# Drobit_V2_0.net
KiCad netlist of a schematic drawn in EAGLE
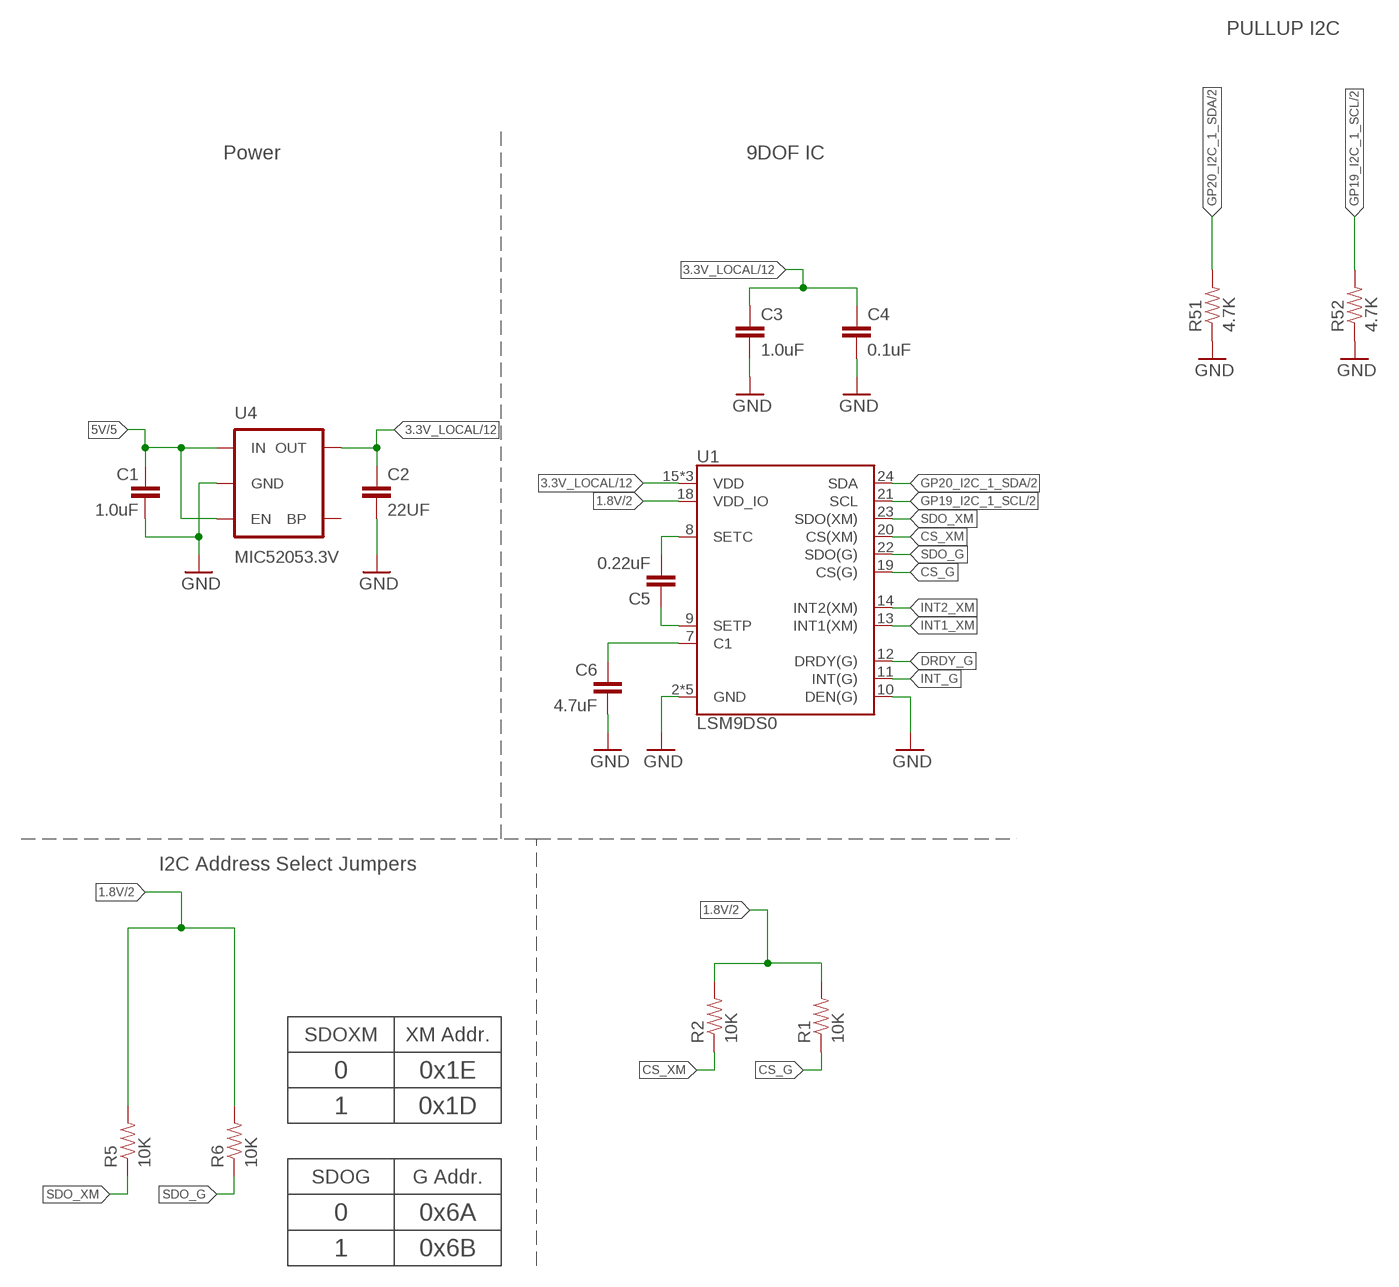
[diagram p0: schematic, sheet 1]
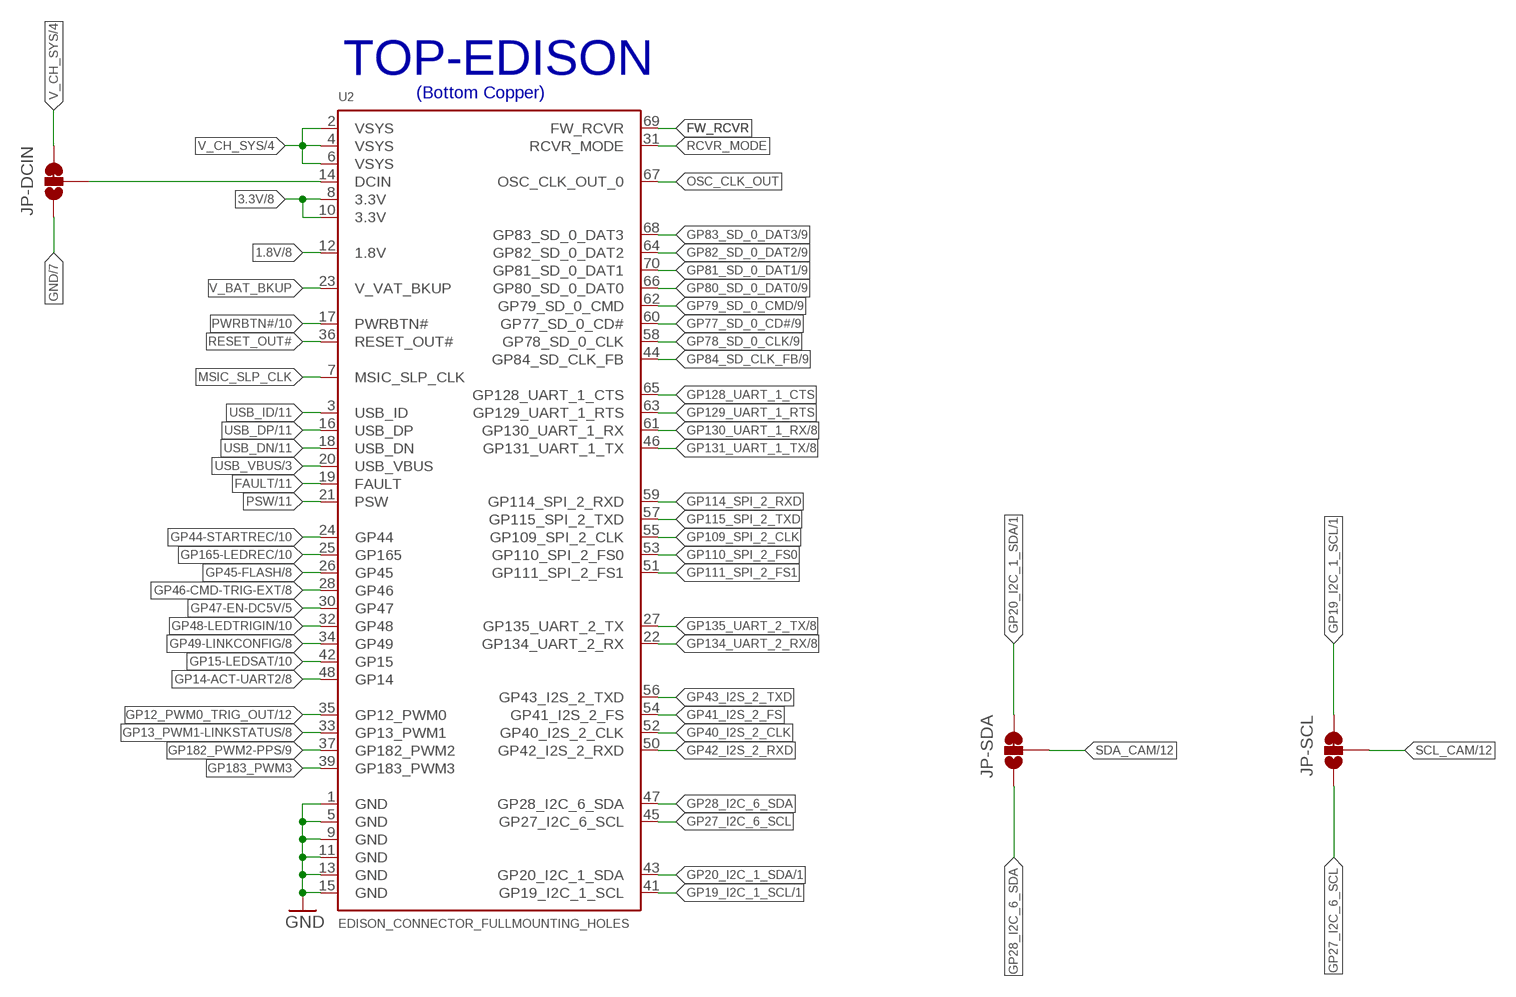
[diagram p1: schematic, sheet 2]
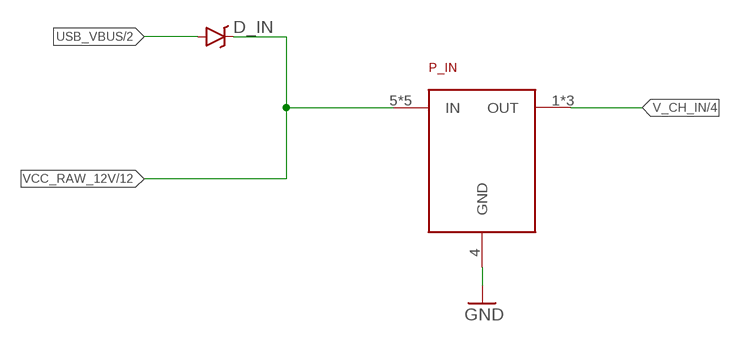
[diagram p2: schematic, sheet 3]
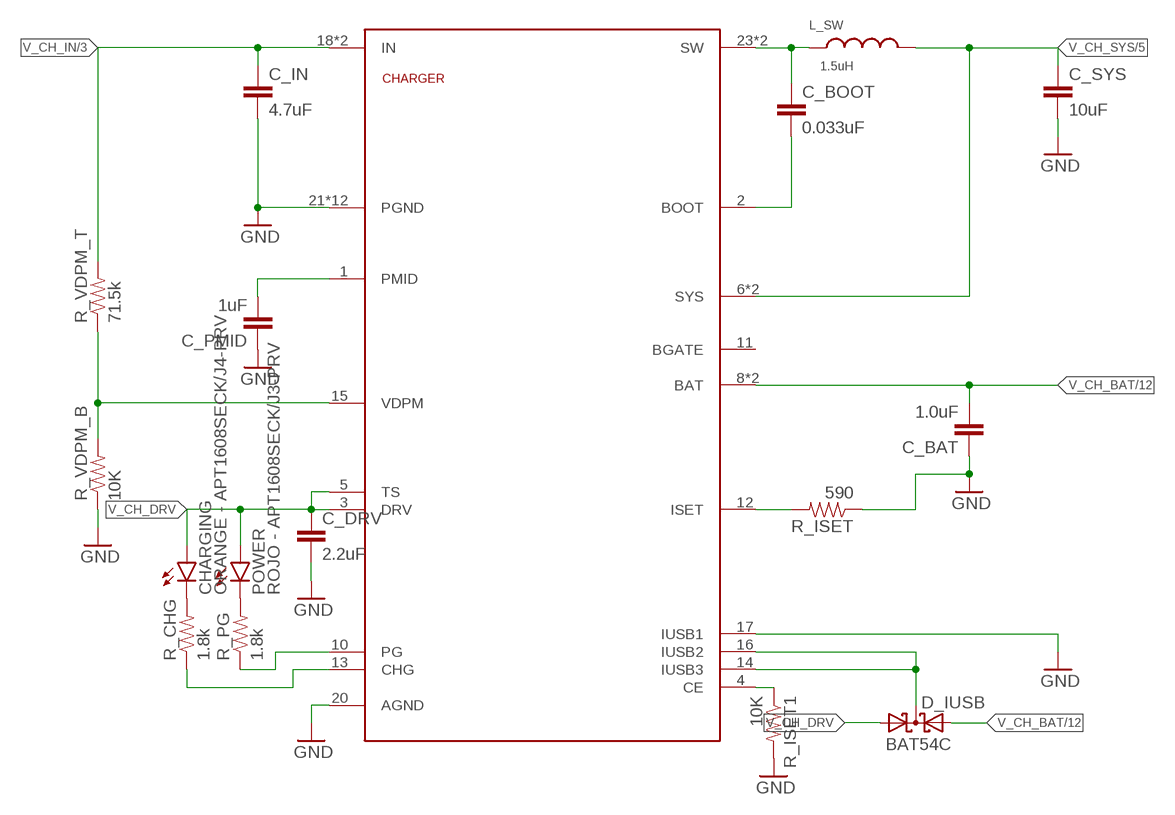
[diagram p3: schematic, sheet 4]
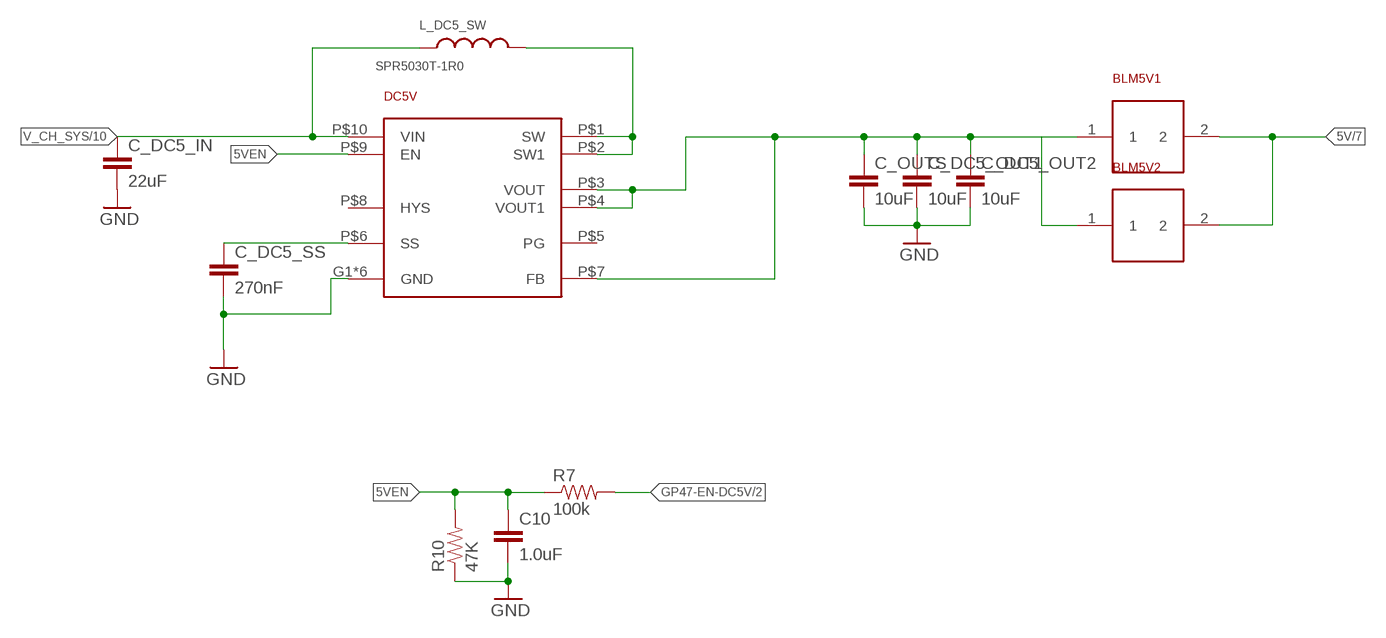
[diagram p4: schematic, sheet 5]
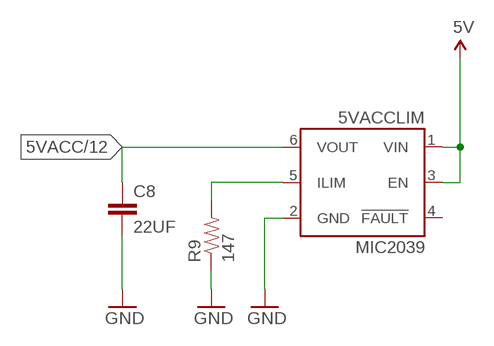
[diagram p5: schematic, sheet 6]
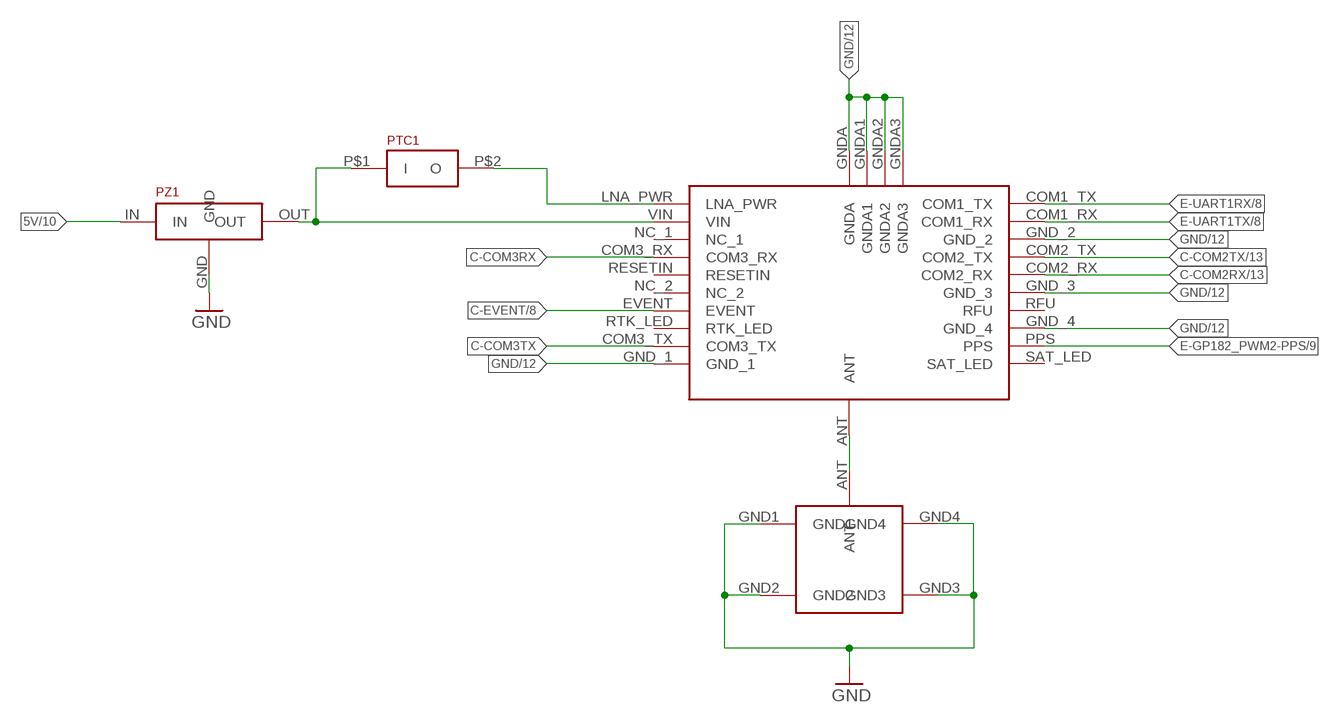
[diagram p6: schematic, sheet 7]
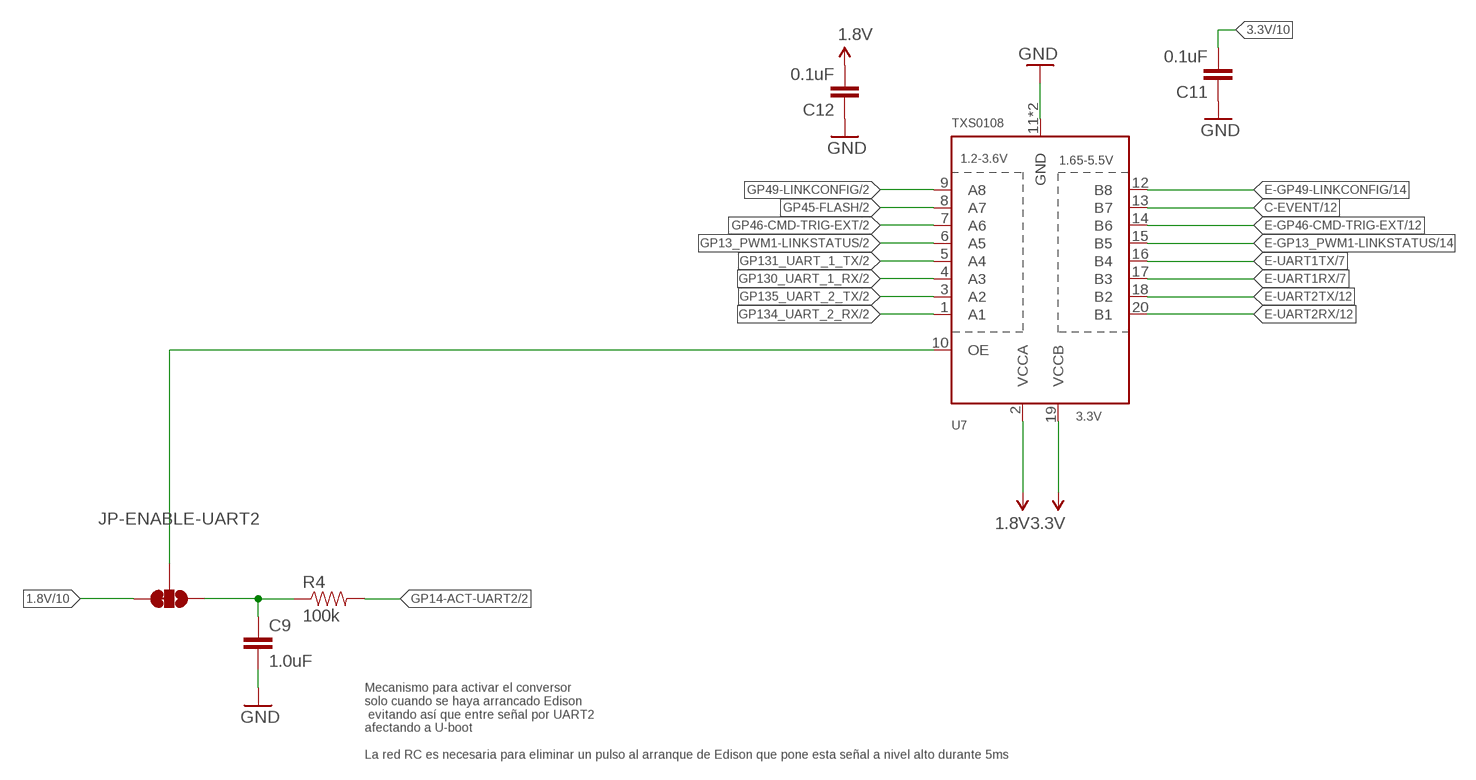
[diagram p7: schematic, sheet 8]
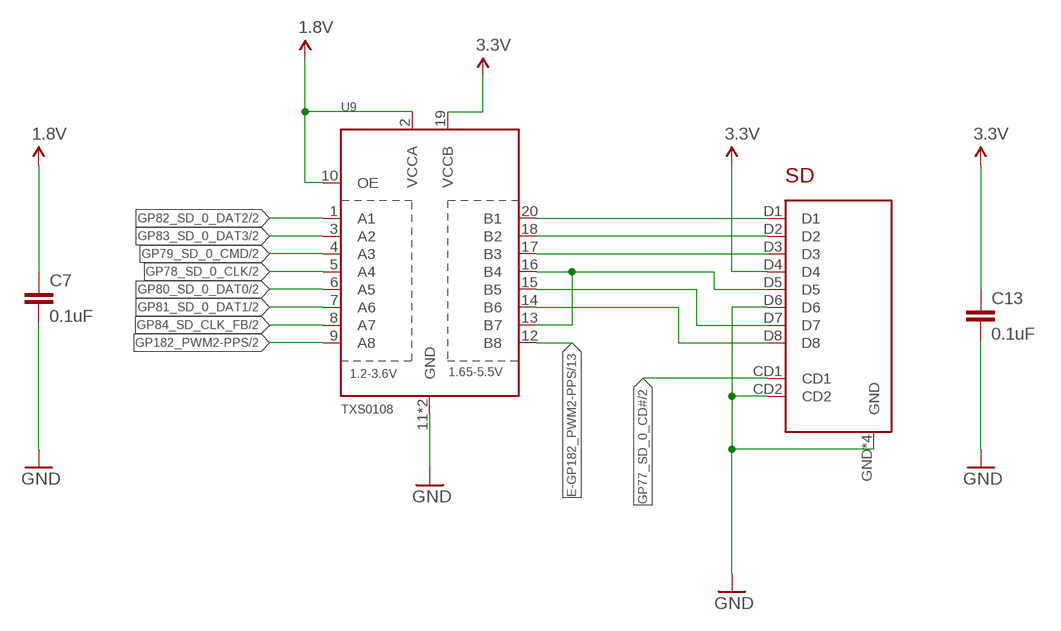
[diagram p8: schematic, sheet 9]
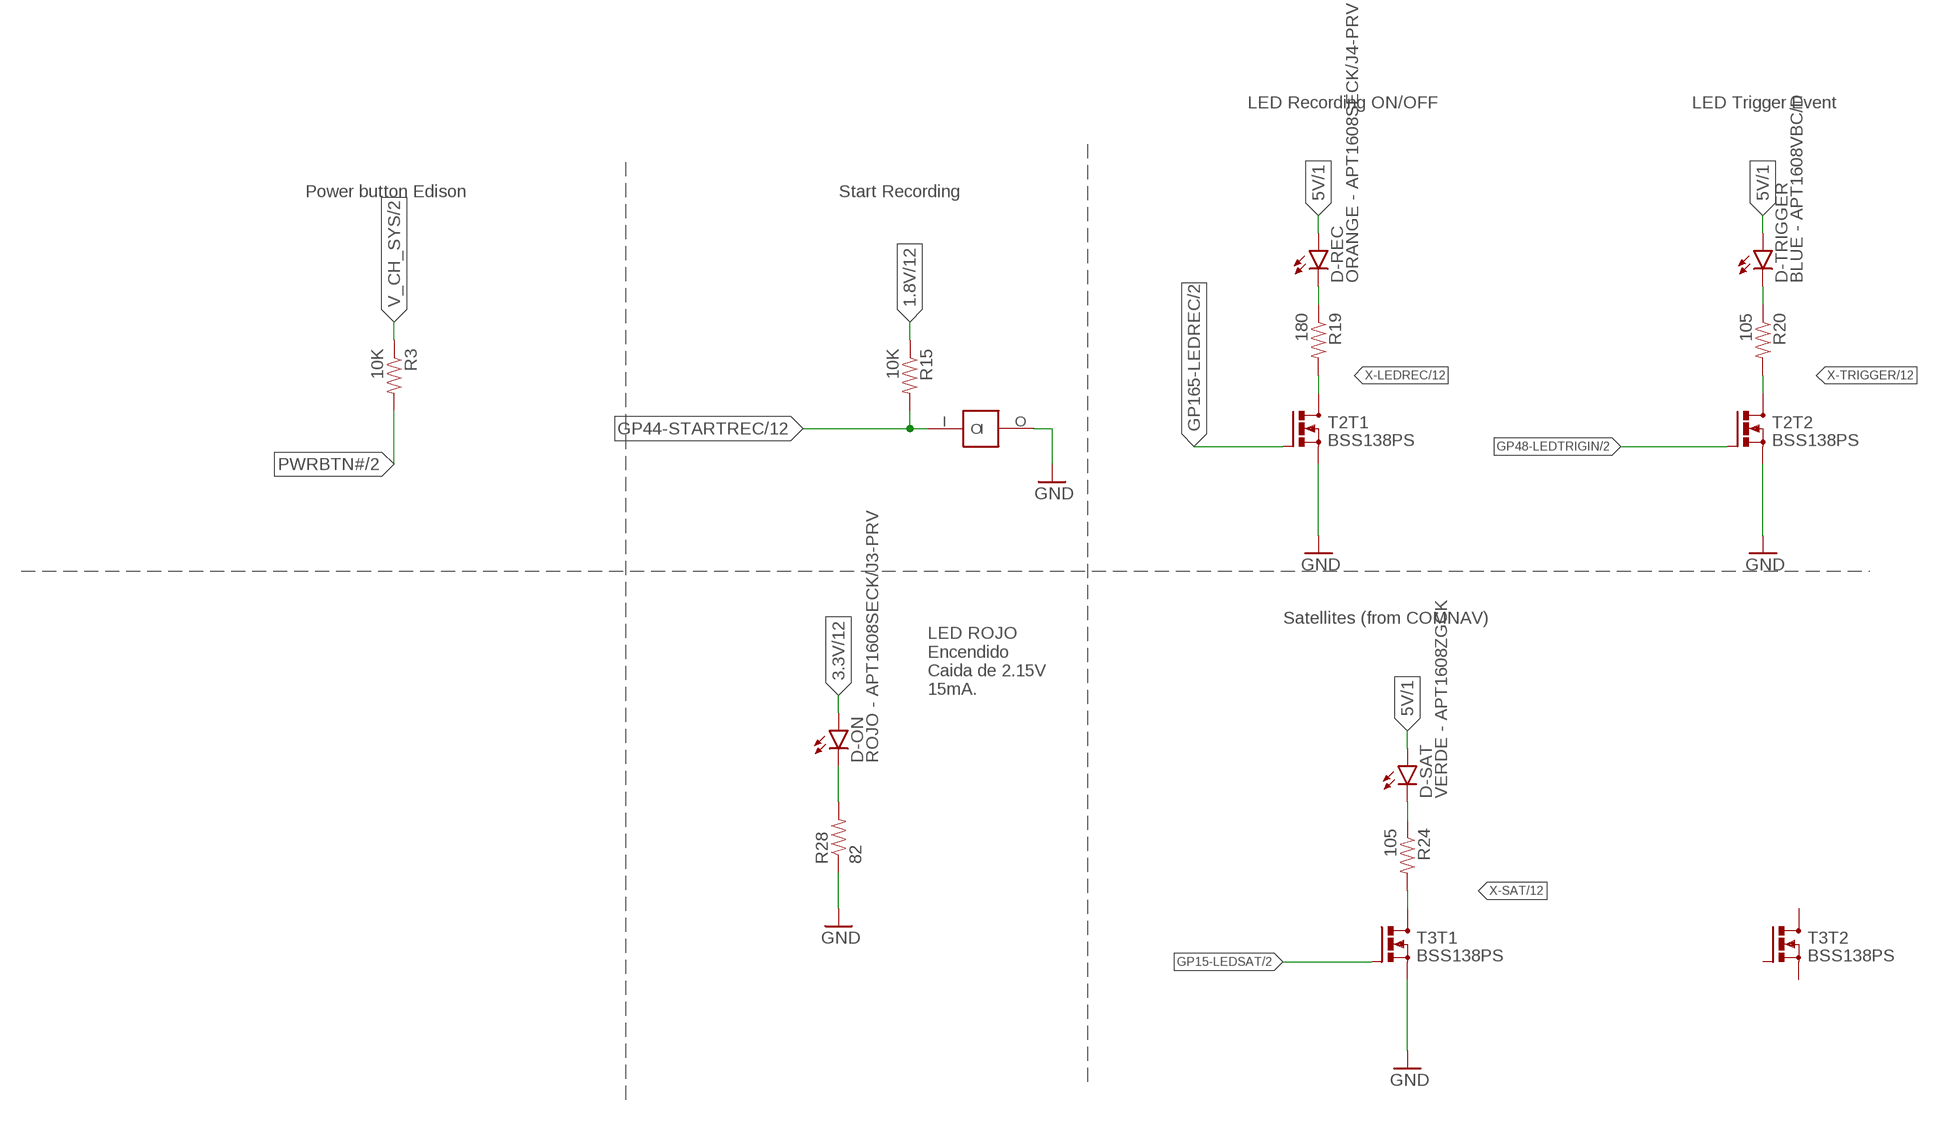
[diagram p9: schematic, sheet 10]
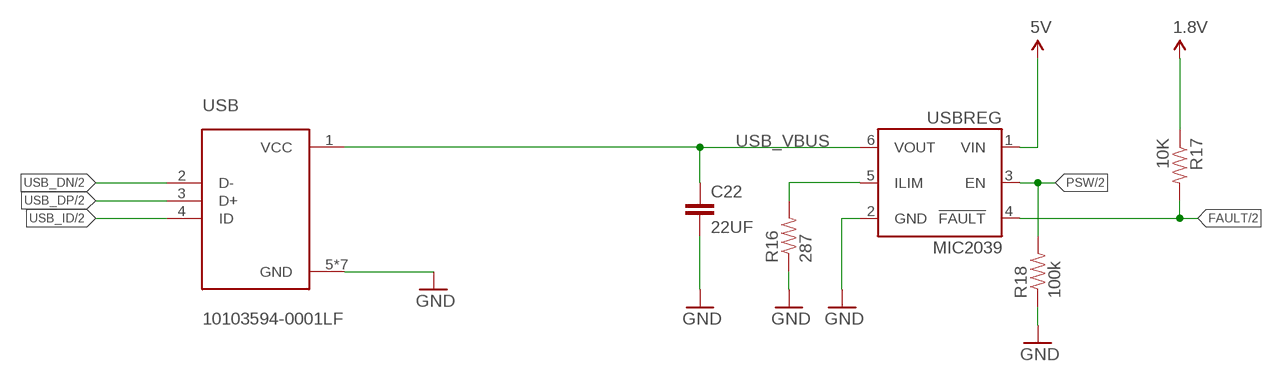
[diagram p10: schematic, sheet 11]
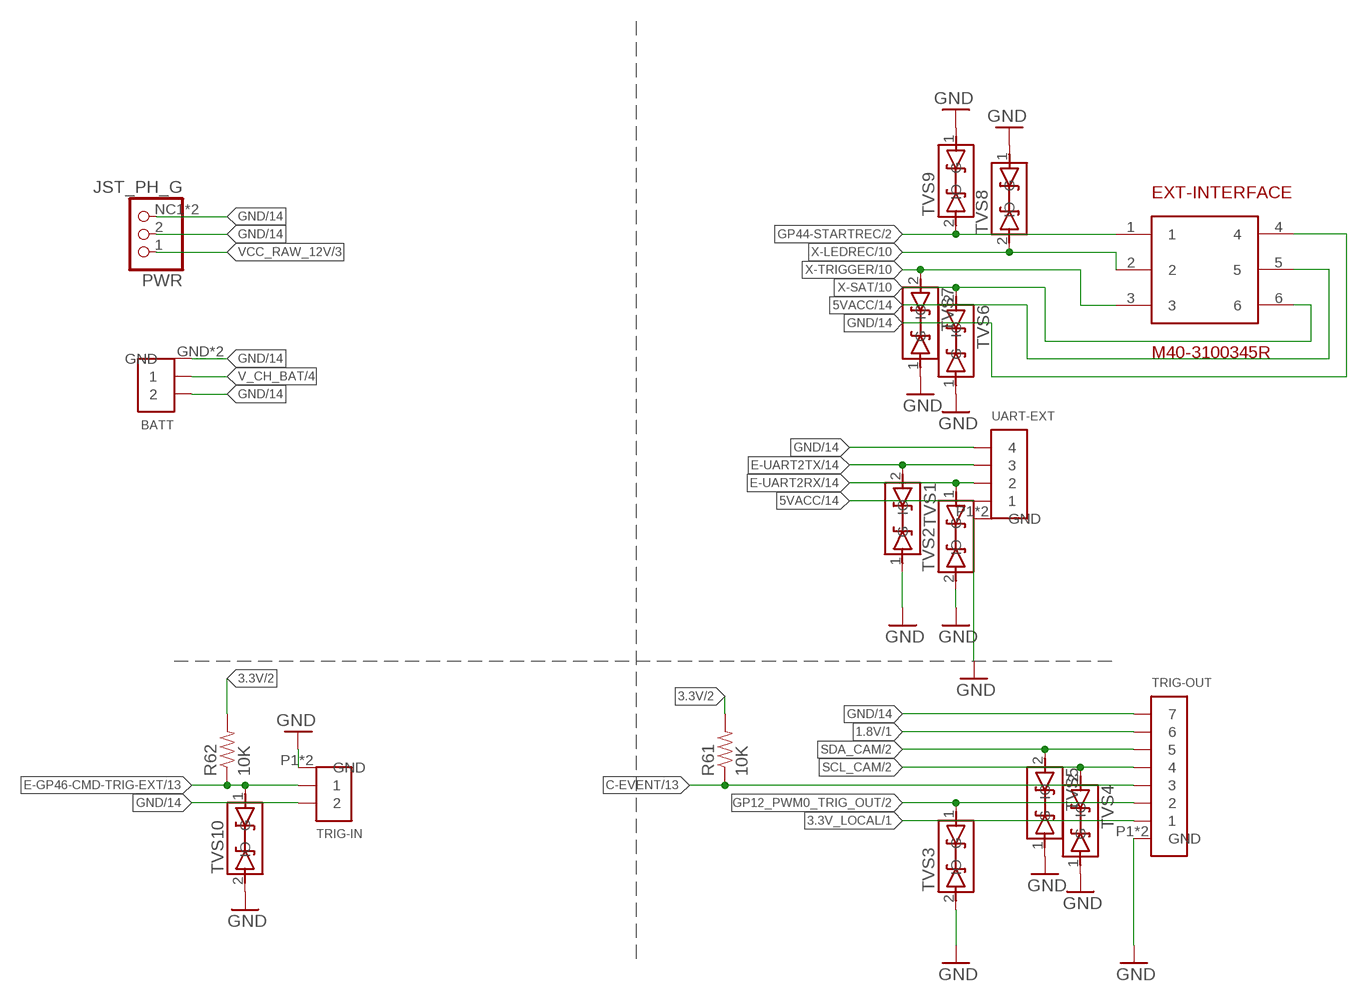
[diagram p11: schematic, sheet 12]
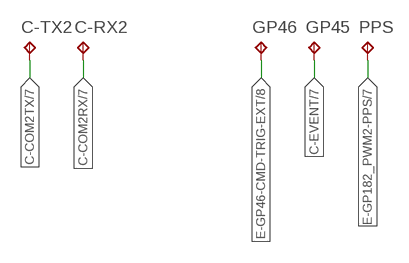
[diagram p12: schematic, sheet 13]
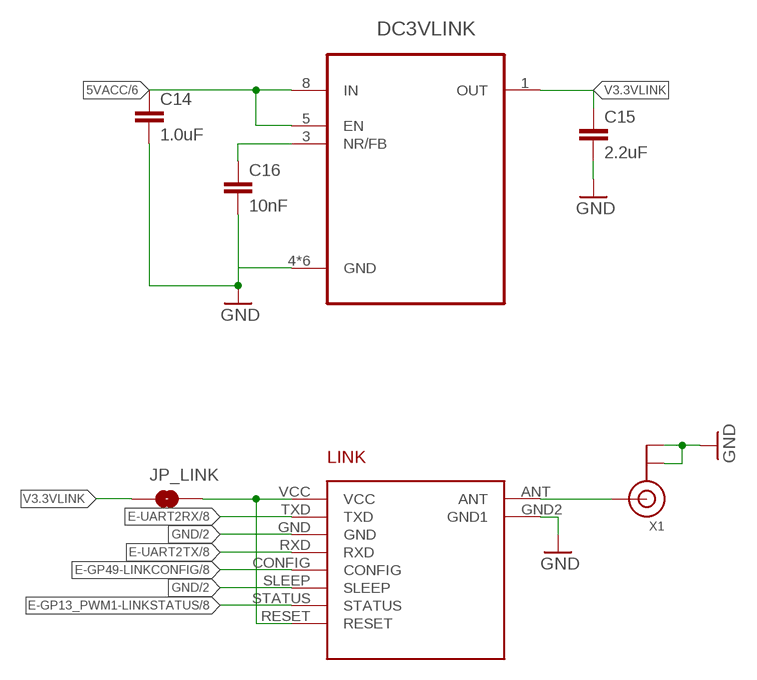
[diagram p13: schematic, sheet 14]

(export (version "E")
  (design (tool "Eeschema 10.0.6"))
  (components
    (comp (ref "C14")
      (value "1.0uF")
      (footprint "eagle-import:0603-CAP")
      (fields (field (name "PARTNO") "810-CGA3E1X7R1E105K"))
      (libsource (lib "eagle-import") (part "1.0UF-16V-10%(0603)"))
    )
    (comp (ref "C15")
      (value "2.2uF")
      (footprint "eagle-import:0603-CAP")
      (fields (field (name "PARTNO") "810-CGA3E1X5R1C225K"))
      (libsource (lib "eagle-import") (part "2.2UF-10V-20%(0603)"))
    )
    (comp (ref "C16")
      (value "10nF")
      (footprint "eagle-import:0603-CAP")
      (fields (field (name "PARTNO") "810-CGA3E2X7R1H103K"))
      (libsource (lib "eagle-import") (part "10NF/10000PF-50V-10%(0603)"))
    )
    (comp (ref "DC3VLINK")
      (value "TPS73501DRBT")
      (footprint "eagle-import:SON65P300X300X100-9N")
      (fields (field (name "PARTNO") "595-TPS73501DRBR"))
      (libsource (lib "eagle-import") (part "TPS73501DRBT"))
    )
    (comp (ref "JP_LINK")
      (value "JUMPER-PAD-2-NOYES_SILK")
      (footprint "eagle-import:PAD-JUMPER-2-NO_YES_SILK")
      (libsource (lib "eagle-import") (part "JUMPER-PAD-2-NOYES_SILK"))
    )
    (comp (ref "LINK")
      (value "HM-TRLR-S")
      (footprint "eagle-import:HM-TRLR-S")
      (libsource (lib "eagle-import") (part "HM-TRLR-S"))
    )
    (comp (ref "X1")
      (value "ANTENNA_U.FL-A-1JB")
      (footprint "eagle-import:U.FL-A-1JB")
      (fields (field (name "PARTNO") "523-A-1JB"))
      (libsource (lib "eagle-import") (part "ANTENNA_U.FL-A-1JB"))
    )
    (comp (ref "5VACCLIM")
      (value "MIC2039")
      (footprint "eagle-import:SOT23-6")
      (fields (field (name "PARTNO") "998-MIC2039EYM6T5"))
      (libsource (lib "eagle-import") (part "MIC2039"))
    )
    (comp (ref "C8")
      (value "22UF")
      (footprint "eagle-import:0603-CAP")
      (fields (field (name "PARTNO") "810-C1608X5R1A226M"))
      (libsource (lib "eagle-import") (part "22UF-10V(0603)"))
    )
    (comp (ref "R9")
      (value "147")
      (footprint "eagle-import:0603-RES")
      (fields (field (name "PARTNO") "754-RR0816P-1470D17A"))
      (libsource (lib "eagle-import") (part "147OHM-1/16W-1%(0603)"))
    )
    (comp (ref "JP-DCIN")
      (value "JUMPER-PAD-3-2OF3_NC_BY_TRACE_SMALL")
      (footprint "eagle-import:PAD-JUMPER-3-2OF3_NC_BY_TRACE_YES_SILK_FULL_BOX")
      (libsource (lib "eagle-import") (part "JUMPER-PAD-3-2OF3_NC_BY_TRACE_SMALL"))
    )
    (comp (ref "JP-SCL")
      (value "JUMPER-PAD-3-2OF3_NC_BY_TRACE_SMALL")
      (footprint "eagle-import:PAD-JUMPER-3-2OF3_NC_BY_TRACE_YES_SILK_FULL_BOX")
      (libsource (lib "eagle-import") (part "JUMPER-PAD-3-2OF3_NC_BY_TRACE_SMALL"))
    )
    (comp (ref "JP-SDA")
      (value "JUMPER-PAD-3-2OF3_NC_BY_TRACE_SMALL")
      (footprint "eagle-import:PAD-JUMPER-3-2OF3_NC_BY_TRACE_YES_SILK_FULL_BOX")
      (libsource (lib "eagle-import") (part "JUMPER-PAD-3-2OF3_NC_BY_TRACE_SMALL"))
    )
    (comp (ref "U2")
      (value "EDISON_CONNECTOR_FULLMOUNTING_HOLES")
      (footprint "eagle-import:EDISON_DAUGHTER")
      (fields (field (name "PARTNO") "798-DF40C70DS04V51"))
      (libsource (lib "eagle-import") (part "EDISON_CONNECTOR_FULLMOUNTING_HOLES"))
    )
    (comp (ref "D-ON")
      (value "ROJO - APT1608SECK/J3-PRV")
      (footprint "eagle-import:LED-0603")
      (fields (field (name "PARTNO") "604-APT1608SECKJ3PRV"))
      (libsource (lib "eagle-import") (part "LED0603"))
    )
    (comp (ref "D-REC")
      (value "ORANGE - APT1608SECK/J4-PRV")
      (footprint "eagle-import:LED-0603")
      (fields (field (name "PARTNO") "604-APT1608SECKJ4PRV"))
      (libsource (lib "eagle-import") (part "LED0603"))
    )
    (comp (ref "D-SAT")
      (value "VERDE - APT1608ZGCK")
      (footprint "eagle-import:LED-0603")
      (fields (field (name "PARTNO") "604-APT1608ZGCK"))
      (libsource (lib "eagle-import") (part "LED0603"))
    )
    (comp (ref "D-TRIGGER")
      (value "BLUE - APT1608VBC/D")
      (footprint "eagle-import:LED-0603")
      (fields (field (name "PARTNO") "604-APT1608VBC/D"))
      (libsource (lib "eagle-import") (part "LED0603"))
    )
    (comp (ref "R3")
      (value "10K")
      (footprint "eagle-import:0603-RES")
      (fields (field (name "PARTNO") "667-ERJ-3EKF1002V"))
      (libsource (lib "eagle-import") (part "10KOHM-1/10W-1%(0603)0603"))
    )
    (comp (ref "R15")
      (value "10K")
      (footprint "eagle-import:0603-RES")
      (fields (field (name "PARTNO") "667-ERJ-3EKF1002V"))
      (libsource (lib "eagle-import") (part "10KOHM-1/10W-1%(0603)0603"))
    )
    (comp (ref "R19")
      (value "180")
      (footprint "eagle-import:0603-RES")
      (fields (field (name "PARTNO") "667-ERJ-3GEYJ181V"))
      (libsource (lib "eagle-import") (part "180OHM1/10W1%(0603)"))
    )
    (comp (ref "R20")
      (value "105")
      (footprint "eagle-import:0603-RES")
      (fields (field (name "PARTNO") "667-ERJ-3EKF1050V"))
      (libsource (lib "eagle-import") (part "105OHM-1/10W-1%(0603)"))
    )
    (comp (ref "R24")
      (value "105")
      (footprint "eagle-import:0603-RES")
      (fields (field (name "PARTNO") "667-ERJ-3EKF1050V"))
      (libsource (lib "eagle-import") (part "105OHM-1/10W-1%(0603)"))
    )
    (comp (ref "R28")
      (value "82")
      (footprint "eagle-import:0603-RES")
      (fields (field (name "PARTNO") "667-ERJ-3EKF82R0V"))
      (libsource (lib "eagle-import") (part "82OHM-1/10W-1%(0603)SMD"))
    )
    (comp (ref "SREC")
      (value "SKRKAEE010")
      (footprint "eagle-import:SKRKAEE010")
      (fields (field (name "PARTNO") "688-SKRKAE"))
      (libsource (lib "eagle-import") (part "SKRKAEE010"))
    )
    (comp (ref "T2")
      (value "BSS138PS")
      (footprint "eagle-import:SOT363")
      (fields (field (name "MF") "NXP Semiconductors") (field (name "PARTNO") "771-BSS138BKS115"))
      (libsource (lib "eagle-import") (part "BSS138PS"))
    )
    (comp (ref "T3")
      (value "BSS138PS")
      (footprint "eagle-import:SOT363")
      (fields (field (name "MF") "NXP Semiconductors") (field (name "PARTNO") "771-BSS138BKS115"))
      (libsource (lib "eagle-import") (part "BSS138PS"))
    )
    (comp (ref "C7")
      (value "0.1uF")
      (footprint "eagle-import:0603-CAP")
      (fields (field (name "PARTNO") "810-CGA3E2X7R1E104K"))
      (libsource (lib "eagle-import") (part "0.1UF-25V(+80/-20%)(0603)"))
    )
    (comp (ref "C13")
      (value "0.1uF")
      (footprint "eagle-import:0603-CAP")
      (fields (field (name "PARTNO") "810-CGA3E2X7R1E104K"))
      (libsource (lib "eagle-import") (part "0.1UF-25V(+80/-20%)(0603)"))
    )
    (comp (ref "SD")
      (value "SDCARD")
      (footprint "eagle-import:1040310811")
      (fields (field (name "PARTNO") "538-104031-0811"))
      (libsource (lib "eagle-import") (part "SDCARD"))
    )
    (comp (ref "U9")
      (value "TXS0108")
      (footprint "eagle-import:R-PVQFN-N20")
      (fields (field (name "PARTNO") "595-TXS0108ERGYR"))
      (libsource (lib "eagle-import") (part "TXS0108"))
    )
    (comp (ref "PTC1")
      (value "0603L010YR")
      (footprint "eagle-import:0602")
      (fields (field (name "PARTNO") "576-0603L010YR"))
      (libsource (lib "eagle-import") (part "0603L010YR"))
    )
    (comp (ref "PZ1")
      (value "ZEN056V230A16YC")
      (footprint "eagle-import:ZEN056V230A16YC")
      (fields (field (name "PARTNO") "650-ZEN056V230A16YC"))
      (libsource (lib "eagle-import") (part "ZEN056V230A16YC"))
    )
    (comp (ref "U$1")
      (value "COMNAV_501G")
      (footprint "eagle-import:COMNAV_501G")
      (libsource (lib "eagle-import") (part "COMNAV_501G"))
    )
    (comp (ref "U$2")
      (value "MCX-TECON-1-1337586-0")
      (footprint "eagle-import:1-1337586-0")
      (fields (field (name "PARTNO") "571-1-1337586-0"))
      (libsource (lib "eagle-import") (part "MCX-TECON-1-1337586-0"))
    )
    (comp (ref "C22")
      (value "22UF")
      (footprint "eagle-import:0603-CAP")
      (fields (field (name "PARTNO") "810-C1608X5R1A226M"))
      (libsource (lib "eagle-import") (part "22UF-10V(0603)"))
    )
    (comp (ref "R16")
      (value "287")
      (footprint "eagle-import:0603-RES")
      (fields (field (name "PARTNO") "667-ERJ-3EKF2870V"))
      (libsource (lib "eagle-import") (part "287OHM-1/10W-1%(0603)"))
    )
    (comp (ref "R17")
      (value "10K")
      (footprint "eagle-import:0603-RES")
      (fields (field (name "PARTNO") "667-ERJ-3EKF1002V"))
      (libsource (lib "eagle-import") (part "10KOHM-1/10W-1%(0603)0603"))
    )
    (comp (ref "R18")
      (value "100k")
      (footprint "eagle-import:0603-RES")
      (fields (field (name "PARTNO") "594-MCT06030C1003FP5"))
      (libsource (lib "eagle-import") (part "100KOHM-1/10W-1%(0603)"))
    )
    (comp (ref "USB")
      (value "10103594-0001LF")
      (footprint "eagle-import:POS-5")
      (fields (field (name "MF") "FCI") (field (name "PARTNO") "649-10103594-0001LF"))
      (libsource (lib "eagle-import") (part "10103594-0001LF"))
    )
    (comp (ref "USBREG")
      (value "MIC2039")
      (footprint "eagle-import:SOT23-6")
      (fields (field (name "PARTNO") "998-MIC2039EYM6T5"))
      (libsource (lib "eagle-import") (part "MIC2039"))
    )
    (comp (ref "BLM5V1")
      (value "BLM18SG221TZ1-2.5A")
      (footprint "eagle-import:0603")
      (fields (field (name "PARTNO") "81-BLM18SG221TZ1D"))
      (libsource (lib "eagle-import") (part "BLM18SG221TZ1-2.5A"))
    )
    (comp (ref "BLM5V2")
      (value "BLM18SG221TZ1-2.5A")
      (footprint "eagle-import:0603")
      (fields (field (name "PARTNO") "81-BLM18SG221TZ1D"))
      (libsource (lib "eagle-import") (part "BLM18SG221TZ1-2.5A"))
    )
    (comp (ref "C10")
      (value "1.0uF")
      (footprint "eagle-import:0603-CAP")
      (fields (field (name "PARTNO") "810-CGA3E1X7R1E105K"))
      (libsource (lib "eagle-import") (part "1.0UF-16V-10%(0603)"))
    )
    (comp (ref "C_DC5_IN")
      (value "22uF")
      (footprint "eagle-import:1210")
      (fields (field (name "PARTNO") "81-GRM32ER61E226ME5L"))
      (libsource (lib "eagle-import") (part "22UF-25V-20%-(1210)"))
    )
    (comp (ref "C_DC5_OUT1")
      (value "10uF")
      (footprint "eagle-import:1210")
      (fields (field (name "PARTNO") "810-C3225X7R1E106K"))
      (libsource (lib "eagle-import") (part "10UF10V10%(1210)"))
    )
    (comp (ref "C_DC5_OUT2")
      (value "10uF")
      (footprint "eagle-import:1210")
      (fields (field (name "PARTNO") "810-C3225X7R1E106K"))
      (libsource (lib "eagle-import") (part "10UF10V10%(1210)"))
    )
    (comp (ref "C_DC5_SS")
      (value "270nF")
      (footprint "eagle-import:0603-CAP")
      (fields (field (name "PARTNO") "81-GRM188R71C274KA1D"))
      (libsource (lib "eagle-import") (part "270NF-16V(0603)"))
    )
    (comp (ref "C_OUTS")
      (value "10uF")
      (footprint "eagle-import:1210")
      (fields (field (name "PARTNO") "810-C3225X7R1E106K"))
      (libsource (lib "eagle-import") (part "10UF10V10%(1210)"))
    )
    (comp (ref "DC5V")
      (value "TPS61232")
      (footprint "eagle-import:SON-10")
      (fields (field (name "PARTNO") "595-TPS61232DRCR"))
      (libsource (lib "eagle-import") (part "TPS61232"))
    )
    (comp (ref "L_DC5_SW")
      (value "SPR5030T-1R0")
      (footprint "eagle-import:SRP5030T-1R0")
      (fields (field (name "PARTNO") "652-SRP5030T-1R0M"))
      (libsource (lib "eagle-import") (part "SPR5030T-1R0"))
    )
    (comp (ref "R7")
      (value "100k")
      (footprint "eagle-import:0603-RES")
      (fields (field (name "PARTNO") "594-MCT06030C1003FP5"))
      (libsource (lib "eagle-import") (part "100KOHM-1/10W-1%(0603)"))
    )
    (comp (ref "R10")
      (value "47K")
      (footprint "eagle-import:0603-RES")
      (fields (field (name "PARTNO") "NO_PONER"))
      (libsource (lib "eagle-import") (part "47KOHM1/10W1%(0603)"))
    )
    (comp (ref "C9")
      (value "1.0uF")
      (footprint "eagle-import:0603-CAP")
      (fields (field (name "PARTNO") "810-CGA3E1X7R1E105K"))
      (libsource (lib "eagle-import") (part "1.0UF-16V-10%(0603)"))
    )
    (comp (ref "C11")
      (value "0.1uF")
      (footprint "eagle-import:0603-CAP")
      (fields (field (name "PARTNO") "810-CGA3E2X7R1E104K"))
      (libsource (lib "eagle-import") (part "0.1UF-25V(+80/-20%)(0603)"))
    )
    (comp (ref "C12")
      (value "0.1uF")
      (footprint "eagle-import:0603-CAP")
      (fields (field (name "PARTNO") "810-CGA3E2X7R1E104K"))
      (libsource (lib "eagle-import") (part "0.1UF-25V(+80/-20%)(0603)"))
    )
    (comp (ref "JP-ENABLE-UART2")
      (value "JUMPER-PAD-3-2OF3_NC_BY_TRACE_SMALL")
      (footprint "eagle-import:PAD-JUMPER-3-2OF3_NC_BY_TRACE_YES_SILK_FULL_BOX")
      (libsource (lib "eagle-import") (part "JUMPER-PAD-3-2OF3_NC_BY_TRACE_SMALL"))
    )
    (comp (ref "R4")
      (value "100k")
      (footprint "eagle-import:0603-RES")
      (fields (field (name "PARTNO") "594-MCT06030C1003FP5"))
      (libsource (lib "eagle-import") (part "100KOHM-1/10W-1%(0603)"))
    )
    (comp (ref "U7")
      (value "TXS0108")
      (footprint "eagle-import:R-PVQFN-N20")
      (fields (field (name "PARTNO") "595-TXS0108ERGYR"))
      (libsource (lib "eagle-import") (part "TXS0108"))
    )
    (comp (ref "D_IN")
      (value "V8PAN50-M3/I")
      (footprint "eagle-import:V8PAN50-M3_I")
      (fields (field (name "PARTNO") "NO_PONER"))
      (libsource (lib "eagle-import") (part "V8PAN50-M3/I"))
    )
    (comp (ref "P_IN")
      (value "FR014H5JZ")
      (footprint "eagle-import:FR014H5JZ")
      (fields (field (name "PARTNO") "512-FR014H5JZ"))
      (libsource (lib "eagle-import") (part "FR014H5JZ"))
    )
    (comp (ref "C-RX2")
      (value "TPTP08R")
      (footprint "eagle-import:TP08R")
      (libsource (lib "eagle-import") (part "TPTP08R"))
    )
    (comp (ref "C-TX2")
      (value "TPTP08R")
      (footprint "eagle-import:TP08R")
      (libsource (lib "eagle-import") (part "TPTP08R"))
    )
    (comp (ref "GP45")
      (value "TPTP08R")
      (footprint "eagle-import:TP08R")
      (libsource (lib "eagle-import") (part "TPTP08R"))
    )
    (comp (ref "GP46")
      (value "TPTP08R")
      (footprint "eagle-import:TP08R")
      (libsource (lib "eagle-import") (part "TPTP08R"))
    )
    (comp (ref "PPS")
      (value "TPTP08R")
      (footprint "eagle-import:TP08R")
      (libsource (lib "eagle-import") (part "TPTP08R"))
    )
    (comp (ref "BATT")
      (value "CONN_2-1-SFH")
      (footprint "eagle-import:SM02B-SFHRS-TF")
      (fields (field (name "PARTNO") "455-2524-1-ND"))
      (libsource (lib "eagle-import") (part "CONN_2-1-SFH"))
    )
    (comp (ref "EXT-INTERFACE")
      (value "M40-3100345R")
      (footprint "eagle-import:M40-3100345R")
      (fields (field (name "PARTNO") "855-M40-3100345R"))
      (libsource (lib "eagle-import") (part "M40-3100345R"))
    )
    (comp (ref "PWR")
      (value "JST_PH_G")
      (footprint "eagle-import:JST-PH-2-SMT-RA")
      (fields (field (name "PARTNO") "455-1749-1-ND"))
      (libsource (lib "eagle-import") (part "JST_PH_G"))
    )
    (comp (ref "R61")
      (value "10K")
      (footprint "eagle-import:0603-RES")
      (fields (field (name "PARTNO") "667-ERJ-3EKF1002V"))
      (libsource (lib "eagle-import") (part "10KOHM-1/10W-1%(0603)0603"))
    )
    (comp (ref "R62")
      (value "10K")
      (footprint "eagle-import:0603-RES")
      (fields (field (name "PARTNO") "667-ERJ-3EKF1002V"))
      (libsource (lib "eagle-import") (part "10KOHM-1/10W-1%(0603)0603"))
    )
    (comp (ref "TRIG-IN")
      (value "CONN_2-1")
      (footprint "eagle-import:JST-GH-2")
      (fields (field (name "PARTNO") "455-1564-1-ND"))
      (libsource (lib "eagle-import") (part "CONN_2-1"))
    )
    (comp (ref "TRIG-OUT")
      (value "CONN_7-1")
      (footprint "eagle-import:JST-GH-7")
      (fields (field (name "PARTNO") "455-1569-1-ND"))
      (libsource (lib "eagle-import") (part "CONN_7-1"))
    )
    (comp (ref "TVS1")
      (value "LXES15AAA1-133")
      (footprint "eagle-import:1005")
      (fields (field (name "PARTNO") "81-LXES15AAA1-133"))
      (libsource (lib "eagle-import") (part "LXES15AAA1-133"))
    )
    (comp (ref "TVS2")
      (value "LXES15AAA1-133")
      (footprint "eagle-import:1005")
      (fields (field (name "PARTNO") "81-LXES15AAA1-133"))
      (libsource (lib "eagle-import") (part "LXES15AAA1-133"))
    )
    (comp (ref "TVS3")
      (value "LXES15AAA1-133")
      (footprint "eagle-import:1005")
      (fields (field (name "PARTNO") "81-LXES15AAA1-133"))
      (libsource (lib "eagle-import") (part "LXES15AAA1-133"))
    )
    (comp (ref "TVS4")
      (value "LXES15AAA1-133")
      (footprint "eagle-import:1005")
      (fields (field (name "PARTNO") "81-LXES15AAA1-133"))
      (libsource (lib "eagle-import") (part "LXES15AAA1-133"))
    )
    (comp (ref "TVS5")
      (value "LXES15AAA1-133")
      (footprint "eagle-import:1005")
      (fields (field (name "PARTNO") "81-LXES15AAA1-133"))
      (libsource (lib "eagle-import") (part "LXES15AAA1-133"))
    )
    (comp (ref "TVS6")
      (value "LXES15AAA1-133")
      (footprint "eagle-import:1005")
      (fields (field (name "PARTNO") "81-LXES15AAA1-133"))
      (libsource (lib "eagle-import") (part "LXES15AAA1-133"))
    )
    (comp (ref "TVS7")
      (value "LXES15AAA1-133")
      (footprint "eagle-import:1005")
      (fields (field (name "PARTNO") "81-LXES15AAA1-133"))
      (libsource (lib "eagle-import") (part "LXES15AAA1-133"))
    )
    (comp (ref "TVS8")
      (value "LXES15AAA1-133")
      (footprint "eagle-import:1005")
      (fields (field (name "PARTNO") "81-LXES15AAA1-133"))
      (libsource (lib "eagle-import") (part "LXES15AAA1-133"))
    )
    (comp (ref "TVS9")
      (value "LXES15AAA1-133")
      (footprint "eagle-import:1005")
      (fields (field (name "PARTNO") "81-LXES15AAA1-133"))
      (libsource (lib "eagle-import") (part "LXES15AAA1-133"))
    )
    (comp (ref "TVS10")
      (value "LXES15AAA1-133")
      (footprint "eagle-import:1005")
      (fields (field (name "PARTNO") "81-LXES15AAA1-133"))
      (libsource (lib "eagle-import") (part "LXES15AAA1-133"))
    )
    (comp (ref "UART-EXT")
      (value "CONN_4-1")
      (footprint "eagle-import:JST-GH-4")
      (fields (field (name "PARTNO") "455-1566-1-ND"))
      (libsource (lib "eagle-import") (part "CONN_4-1"))
    )
    (comp (ref "CHARGER")
      (value "BQ24266")
      (footprint "eagle-import:QFN50P400X400X100-25N")
      (fields (field (name "PARTNO") "595-BQ24266RGER"))
      (libsource (lib "eagle-import") (part "BQ24266"))
    )
    (comp (ref "CHARGING")
      (value "ORANGE - APT1608SECK/J4-PRV")
      (footprint "eagle-import:LED-0603")
      (fields (field (name "PARTNO") "604-APT1608SECKJ4PRV"))
      (libsource (lib "eagle-import") (part "LED0603"))
    )
    (comp (ref "C_BAT")
      (value "1.0uF")
      (footprint "eagle-import:0603-CAP")
      (fields (field (name "PARTNO") "810-CGA3E1X7R1E105K"))
      (libsource (lib "eagle-import") (part "1.0UF-16V-10%(0603)"))
    )
    (comp (ref "C_BOOT")
      (value "0.033uF")
      (footprint "eagle-import:0603-CAP")
      (fields (field (name "PARTNO") "810-CGA3E2X7R1H333MA"))
      (libsource (lib "eagle-import") (part "33NF-50V-10%(0603)"))
    )
    (comp (ref "C_DRV")
      (value "2.2uF")
      (footprint "eagle-import:0603-CAP")
      (fields (field (name "PARTNO") "810-CGA3E1X5R1C225K"))
      (libsource (lib "eagle-import") (part "2.2UF-10V-20%(0603)"))
    )
    (comp (ref "C_IN")
      (value "4.7uF")
      (footprint "eagle-import:0603-CAP")
      (fields (field (name "PARTNO") "810-C2012X5R1E226M"))
      (libsource (lib "eagle-import") (part "4.7UF-50V(0603)0603"))
    )
    (comp (ref "C_PMID")
      (value "1uF")
      (footprint "eagle-import:0603-CAP")
      (fields (field (name "PARTNO") "810-CGA3E1X7R1E105K"))
      (libsource (lib "eagle-import") (part "1UF-25V-10%(0603)"))
    )
    (comp (ref "C_SYS")
      (value "10uF")
      (footprint "eagle-import:1210")
      (fields (field (name "PARTNO") "810-C3225X7R1E106K"))
      (libsource (lib "eagle-import") (part "10UF16V10%(1210)"))
    )
    (comp (ref "D_IUSB")
      (value "BAT54C")
      (footprint "eagle-import:SOT23")
      (fields (field (name "PARTNO") "512-BAT54C"))
      (libsource (lib "eagle-import") (part "BAT54C"))
    )
    (comp (ref "L_SW")
      (value "1.5uH")
      (footprint "eagle-import:FDSD0420")
      (fields (field (name "PARTNO") "81-FDSD0420-H-1R5MP3"))
      (libsource (lib "eagle-import") (part "FDSD0420-H-1R5M"))
    )
    (comp (ref "POWER")
      (value "ROJO - APT1608SECK/J3-PRV")
      (footprint "eagle-import:LED-0603")
      (fields (field (name "PARTNO") "604-APT1608SECKJ3PRV"))
      (libsource (lib "eagle-import") (part "LED0603"))
    )
    (comp (ref "R_CHG")
      (value "1.8k")
      (footprint "eagle-import:0603-RES")
      (fields (field (name "PARTNO") "667-ERJ-3GEYJ182V"))
      (libsource (lib "eagle-import") (part "1.8KOHM1/10W1%(0603)"))
    )
    (comp (ref "R_ISET")
      (value "590")
      (footprint "eagle-import:0603-RES")
      (fields (field (name "PARTNO") "754-RR0816P-5900D75A"))
      (libsource (lib "eagle-import") (part "590OHM1/10W1%(0603)"))
    )
    (comp (ref "R_ISET1")
      (value "10K")
      (footprint "eagle-import:0603-RES")
      (fields (field (name "PARTNO") "667-ERJ-3EKF1002V"))
      (libsource (lib "eagle-import") (part "10KOHM-1/10W-1%(0603)0603"))
    )
    (comp (ref "R_PG")
      (value "1.8k")
      (footprint "eagle-import:0603-RES")
      (fields (field (name "PARTNO") "667-ERJ-3GEYJ182V"))
      (libsource (lib "eagle-import") (part "1.8KOHM1/10W1%(0603)"))
    )
    (comp (ref "R_VDPM_B")
      (value "10K")
      (footprint "eagle-import:0603-RES")
      (fields (field (name "PARTNO") "667-ERJ-3EKF1002V"))
      (libsource (lib "eagle-import") (part "10KOHM-1/10W-0.1%(0603)0603"))
    )
    (comp (ref "R_VDPM_T")
      (value "71.5k")
      (footprint "eagle-import:0603-RES")
      (fields (field (name "PARTNO") "667-ERJ-3EKF7152V"))
      (libsource (lib "eagle-import") (part "71.5KOHM1/10W1%(0603)"))
    )
    (comp (ref "C1")
      (value "1.0uF")
      (footprint "eagle-import:0603-CAP")
      (fields (field (name "PARTNO") "810-CGA3E1X7R1E105K"))
      (libsource (lib "eagle-import") (part "1.0UF-16V-10%(0603)"))
    )
    (comp (ref "C2")
      (value "22UF")
      (footprint "eagle-import:0603-CAP")
      (fields (field (name "PARTNO") "810-C1608X5R1A226M"))
      (libsource (lib "eagle-import") (part "22UF-10V(0603)"))
    )
    (comp (ref "C3")
      (value "1.0uF")
      (footprint "eagle-import:0603-CAP")
      (fields (field (name "PARTNO") "810-CGA3E1X7R1E105K"))
      (libsource (lib "eagle-import") (part "1.0UF-16V-10%(0603)"))
    )
    (comp (ref "C4")
      (value "0.1uF")
      (footprint "eagle-import:0603-CAP")
      (fields (field (name "PARTNO") "810-CGA3E2X7R1E104K"))
      (libsource (lib "eagle-import") (part "0.1UF-25V(+80/-20%)(0603)"))
    )
    (comp (ref "C5")
      (value "0.22uF")
      (footprint "eagle-import:0603-CAP")
      (fields (field (name "PARTNO") "810-C1608X7R1C224K"))
      (libsource (lib "eagle-import") (part "0.22UF-16V-10%(0603)"))
    )
    (comp (ref "C6")
      (value "4.7uF")
      (footprint "eagle-import:0603-CAP")
      (fields (field (name "PARTNO") "81-GRM18R60J475KE19D"))
      (libsource (lib "eagle-import") (part "4.7UF-6.3V-10%(0603)0603"))
    )
    (comp (ref "R1")
      (value "10K")
      (footprint "eagle-import:0603-RES")
      (fields (field (name "PARTNO") "667-ERJ-3EKF1002V"))
      (libsource (lib "eagle-import") (part "10KOHM-1/10W-1%(0603)0603"))
    )
    (comp (ref "R2")
      (value "10K")
      (footprint "eagle-import:0603-RES")
      (fields (field (name "PARTNO") "667-ERJ-3EKF1002V"))
      (libsource (lib "eagle-import") (part "10KOHM-1/10W-1%(0603)0603"))
    )
    (comp (ref "R5")
      (value "10K")
      (footprint "eagle-import:0603-RES")
      (fields (field (name "PARTNO") "667-ERJ-3EKF1002V"))
      (libsource (lib "eagle-import") (part "10KOHM-1/10W-1%(0603)0603"))
    )
    (comp (ref "R6")
      (value "10K")
      (footprint "eagle-import:0603-RES")
      (fields (field (name "PARTNO") "667-ERJ-3EKF1002V"))
      (libsource (lib "eagle-import") (part "10KOHM-1/10W-1%(0603)0603"))
    )
    (comp (ref "R51")
      (value "4.7K")
      (footprint "eagle-import:0603-RES")
      (fields (field (name "PARTNO") "NO_PONER"))
      (libsource (lib "eagle-import") (part "4.7KOHM-1/10W-1%(0603)"))
    )
    (comp (ref "R52")
      (value "4.7K")
      (footprint "eagle-import:0603-RES")
      (fields (field (name "PARTNO") "NO_PONER"))
      (libsource (lib "eagle-import") (part "4.7KOHM-1/10W-1%(0603)"))
    )
    (comp (ref "U1")
      (value "LSM9DS0")
      (footprint "eagle-import:LGA-24")
      (fields (field (name "PARTNO") "497-13902-1-ND"))
      (libsource (lib "eagle-import") (part "LSM9DS0"))
    )
    (comp (ref "U4")
      (value "MIC52053.3V")
      (footprint "eagle-import:SOT23-5")
      (fields (field (name "PARTNO") "998-MIC5205-3.3YM5TR"))
      (libsource (lib "eagle-import") (part "MIC52053.3V"))
    )
  )
  (nets
    (net (code "1") (name "1.8V") (class "Default")
      (node (ref "C12") (pin "2") (pinfunction "2_2") (pintype "passive"))
      (node (ref "C7") (pin "1") (pinfunction "1_1") (pintype "passive"))
      (node (ref "JP-ENABLE-UART2") (pin "3") (pinfunction "3_3") (pintype "passive"))
      (node (ref "R1") (pin "2") (pinfunction "2_2") (pintype "passive"))
      (node (ref "R15") (pin "1") (pinfunction "1_1") (pintype "passive"))
      (node (ref "R17") (pin "1") (pinfunction "1_1") (pintype "passive"))
      (node (ref "R2") (pin "2") (pinfunction "2_2") (pintype "passive"))
      (node (ref "R5") (pin "2") (pinfunction "2_2") (pintype "passive"))
      (node (ref "R6") (pin "2") (pinfunction "2_2") (pintype "passive"))
      (node (ref "TRIG-OUT") (pin "6") (pinfunction "6_6") (pintype "bidirectional"))
      (node (ref "U1") (pin "18") (pinfunction "VDD_IO_18") (pintype "bidirectional"))
      (node (ref "U2") (pin "12") (pinfunction "1.8V_12") (pintype "bidirectional"))
      (node (ref "U7") (pin "2") (pinfunction "VCCA_2") (pintype "bidirectional"))
      (node (ref "U9") (pin "10") (pinfunction "OE_10") (pintype "bidirectional"))
      (node (ref "U9") (pin "2") (pinfunction "VCCA_2") (pintype "bidirectional"))
    )
    (net (code "2") (name "3.3V") (class "Default")
      (node (ref "C11") (pin "2") (pinfunction "2_2") (pintype "passive"))
      (node (ref "C13") (pin "1") (pinfunction "1_1") (pintype "passive"))
      (node (ref "D-ON") (pin "A") (pinfunction "A_A") (pintype "passive"))
      (node (ref "R61") (pin "2") (pinfunction "2_2") (pintype "passive"))
      (node (ref "R62") (pin "2") (pinfunction "2_2") (pintype "passive"))
      (node (ref "SD") (pin "D4") (pinfunction "D4_D4") (pintype "bidirectional"))
      (node (ref "U2") (pin "10") (pinfunction "3.3V_10") (pintype "bidirectional"))
      (node (ref "U2") (pin "8") (pinfunction "3.3V_8") (pintype "bidirectional"))
      (node (ref "U7") (pin "19") (pinfunction "VCCB_19") (pintype "bidirectional"))
      (node (ref "U9") (pin "19") (pinfunction "VCCB_19") (pintype "bidirectional"))
    )
    (net (code "3") (name "3.3V_LOCAL") (class "Default")
      (node (ref "C2") (pin "1") (pinfunction "1_1") (pintype "passive"))
      (node (ref "C3") (pin "1") (pinfunction "1_1") (pintype "passive"))
      (node (ref "C4") (pin "1") (pinfunction "1_1") (pintype "passive"))
      (node (ref "TRIG-OUT") (pin "1") (pinfunction "1_1") (pintype "bidirectional"))
      (node (ref "U1") (pin "15") (pinfunction "VDD_15") (pintype "bidirectional"))
      (node (ref "U1") (pin "16") (pinfunction "VDD_16") (pintype "bidirectional"))
      (node (ref "U1") (pin "17") (pinfunction "VDD_17") (pintype "bidirectional"))
      (node (ref "U4") (pin "5") (pinfunction "OUT_5") (pintype "passive"))
    )
    (net (code "4") (name "5V") (class "Default")
      (node (ref "5VACCLIM") (pin "1") (pinfunction "VIN_1") (pintype "bidirectional"))
      (node (ref "5VACCLIM") (pin "3") (pinfunction "EN_3") (pintype "bidirectional"))
      (node (ref "BLM5V1") (pin "2") (pinfunction "2_2") (pintype "bidirectional"))
      (node (ref "BLM5V2") (pin "2") (pinfunction "2_2") (pintype "bidirectional"))
      (node (ref "C1") (pin "1") (pinfunction "1_1") (pintype "passive"))
      (node (ref "D-REC") (pin "A") (pinfunction "A_A") (pintype "passive"))
      (node (ref "D-SAT") (pin "A") (pinfunction "A_A") (pintype "passive"))
      (node (ref "D-TRIGGER") (pin "A") (pinfunction "A_A") (pintype "passive"))
      (node (ref "PZ1") (pin "IN") (pinfunction "IN_IN") (pintype "bidirectional"))
      (node (ref "U4") (pin "1") (pinfunction "IN_1") (pintype "input"))
      (node (ref "U4") (pin "3") (pinfunction "EN_3") (pintype "input"))
      (node (ref "USBREG") (pin "1") (pinfunction "VIN_1") (pintype "bidirectional"))
    )
    (net (code "5") (name "5VACC") (class "Default")
      (node (ref "5VACCLIM") (pin "6") (pinfunction "VOUT_6") (pintype "bidirectional"))
      (node (ref "C14") (pin "1") (pinfunction "1_1") (pintype "passive"))
      (node (ref "C8") (pin "1") (pinfunction "1_1") (pintype "passive"))
      (node (ref "DC3VLINK") (pin "5") (pinfunction "EN_5") (pintype "input"))
      (node (ref "DC3VLINK") (pin "8") (pinfunction "IN_8") (pintype "input"))
      (node (ref "EXT-INTERFACE") (pin "5") (pinfunction "5_5") (pintype "bidirectional"))
      (node (ref "UART-EXT") (pin "1") (pinfunction "1_1") (pintype "bidirectional"))
    )
    (net (code "6") (name "5VEN") (class "Default")
      (node (ref "C10") (pin "1") (pinfunction "1_1") (pintype "passive"))
      (node (ref "DC5V") (pin "P$9") (pinfunction "EN_P$9") (pintype "bidirectional"))
      (node (ref "R10") (pin "2") (pinfunction "2_2") (pintype "passive"))
      (node (ref "R7") (pin "1") (pinfunction "1_1") (pintype "passive"))
    )
    (net (code "7") (name "C-COM2RX") (class "Default")
      (node (ref "C-RX2") (pin "TP") (pinfunction "TP_TP") (pintype "input"))
      (node (ref "U$1") (pin "COM2_RX") (pinfunction "COM2_RX_COM2_RX") (pintype "bidirectional"))
    )
    (net (code "8") (name "C-COM2TX") (class "Default")
      (node (ref "C-TX2") (pin "TP") (pinfunction "TP_TP") (pintype "input"))
      (node (ref "U$1") (pin "COM2_TX") (pinfunction "COM2_TX_COM2_TX") (pintype "bidirectional"))
    )
    (net (code "9") (name "C-COM3RX") (class "Default")
      (node (ref "U$1") (pin "COM3_RX") (pinfunction "COM3_RX_COM3_RX") (pintype "bidirectional"))
    )
    (net (code "10") (name "C-COM3TX") (class "Default")
      (node (ref "U$1") (pin "COM3_TX") (pinfunction "COM3_TX_COM3_TX") (pintype "bidirectional"))
    )
    (net (code "11") (name "C-EVENT") (class "Default")
      (node (ref "GP45") (pin "TP") (pinfunction "TP_TP") (pintype "input"))
      (node (ref "R61") (pin "1") (pinfunction "1_1") (pintype "passive"))
      (node (ref "TRIG-OUT") (pin "3") (pinfunction "3_3") (pintype "bidirectional"))
      (node (ref "U$1") (pin "EVENT") (pinfunction "EVENT_EVENT") (pintype "bidirectional"))
      (node (ref "U7") (pin "13") (pinfunction "B7_13") (pintype "bidirectional"))
    )
    (net (code "12") (name "CS_G") (class "Default")
      (node (ref "R1") (pin "1") (pinfunction "1_1") (pintype "passive"))
      (node (ref "U1") (pin "19") (pinfunction "CS(G)_19") (pintype "bidirectional"))
    )
    (net (code "13") (name "CS_XM") (class "Default")
      (node (ref "R2") (pin "1") (pinfunction "1_1") (pintype "passive"))
      (node (ref "U1") (pin "20") (pinfunction "CS(XM)_20") (pintype "bidirectional"))
    )
    (net (code "14") (name "DRDY_G") (class "Default")
      (node (ref "U1") (pin "12") (pinfunction "DRDY(G)_12") (pintype "bidirectional"))
    )
    (net (code "15") (name "E-GP13_PWM1-LINKSTATUS") (class "Default")
      (node (ref "LINK") (pin "STATUS") (pinfunction "STATUS_STATUS") (pintype "bidirectional"))
      (node (ref "U7") (pin "15") (pinfunction "B5_15") (pintype "bidirectional"))
    )
    (net (code "16") (name "E-GP46-CMD-TRIG-EXT") (class "Default")
      (node (ref "GP46") (pin "TP") (pinfunction "TP_TP") (pintype "input"))
      (node (ref "R62") (pin "1") (pinfunction "1_1") (pintype "passive"))
      (node (ref "TRIG-IN") (pin "1") (pinfunction "1_1") (pintype "bidirectional"))
      (node (ref "TVS10") (pin "1") (pinfunction "G_1") (pintype "bidirectional"))
      (node (ref "U7") (pin "14") (pinfunction "B6_14") (pintype "bidirectional"))
    )
    (net (code "17") (name "E-GP49-LINKCONFIG") (class "Default")
      (node (ref "LINK") (pin "CONFIG") (pinfunction "CONFIG_CONFIG") (pintype "bidirectional"))
      (node (ref "U7") (pin "12") (pinfunction "B8_12") (pintype "bidirectional"))
    )
    (net (code "18") (name "E-GP182_PWM2-PPS") (class "Default")
      (node (ref "PPS") (pin "TP") (pinfunction "TP_TP") (pintype "input"))
      (node (ref "U$1") (pin "PPS") (pinfunction "PPS_PPS") (pintype "bidirectional"))
      (node (ref "U9") (pin "12") (pinfunction "B8_12") (pintype "bidirectional"))
    )
    (net (code "19") (name "E-UART1RX") (class "Default")
      (node (ref "U$1") (pin "COM1_TX") (pinfunction "COM1_TX_COM1_TX") (pintype "bidirectional"))
      (node (ref "U7") (pin "17") (pinfunction "B3_17") (pintype "bidirectional"))
    )
    (net (code "20") (name "E-UART1TX") (class "Default")
      (node (ref "U$1") (pin "COM1_RX") (pinfunction "COM1_RX_COM1_RX") (pintype "bidirectional"))
      (node (ref "U7") (pin "16") (pinfunction "B4_16") (pintype "bidirectional"))
    )
    (net (code "21") (name "E-UART2RX") (class "Default")
      (node (ref "LINK") (pin "TXD") (pinfunction "TXD_TXD") (pintype "bidirectional"))
      (node (ref "TVS2") (pin "1") (pinfunction "G_1") (pintype "bidirectional"))
      (node (ref "U7") (pin "20") (pinfunction "B1_20") (pintype "bidirectional"))
      (node (ref "UART-EXT") (pin "2") (pinfunction "2_2") (pintype "bidirectional"))
    )
    (net (code "22") (name "E-UART2TX") (class "Default")
      (node (ref "LINK") (pin "RXD") (pinfunction "RXD_RXD") (pintype "bidirectional"))
      (node (ref "TVS1") (pin "2") (pinfunction "IO_2") (pintype "bidirectional"))
      (node (ref "U7") (pin "18") (pinfunction "B2_18") (pintype "bidirectional"))
      (node (ref "UART-EXT") (pin "3") (pinfunction "3_3") (pintype "bidirectional"))
    )
    (net (code "23") (name "FAULT") (class "Default")
      (node (ref "R17") (pin "2") (pinfunction "2_2") (pintype "passive"))
      (node (ref "U2") (pin "19") (pinfunction "FAULT_19") (pintype "bidirectional"))
      (node (ref "USBREG") (pin "4") (pinfunction "~{FAULT}_4") (pintype "bidirectional"))
    )
    (net (code "24") (name "FW_RCVR") (class "Default")
      (node (ref "U2") (pin "69") (pinfunction "FW_RCVR_69") (pintype "bidirectional"))
    )
    (net (code "25") (name "GND") (class "Default")
      (node (ref "5VACCLIM") (pin "2") (pinfunction "GND_2") (pintype "bidirectional"))
      (node (ref "BATT") (pin "2") (pinfunction "2_2") (pintype "bidirectional"))
      (node (ref "BATT") (pin "GND") (pinfunction "GND_GND") (pintype "bidirectional"))
      (node (ref "BATT") (pin "GND1") (pinfunction "GND_GND1") (pintype "bidirectional"))
      (node (ref "C1") (pin "2") (pinfunction "2_2") (pintype "passive"))
      (node (ref "C10") (pin "2") (pinfunction "2_2") (pintype "passive"))
      (node (ref "C11") (pin "1") (pinfunction "1_1") (pintype "passive"))
      (node (ref "C12") (pin "1") (pinfunction "1_1") (pintype "passive"))
      (node (ref "C13") (pin "2") (pinfunction "2_2") (pintype "passive"))
      (node (ref "C14") (pin "2") (pinfunction "2_2") (pintype "passive"))
      (node (ref "C15") (pin "2") (pinfunction "2_2") (pintype "passive"))
      (node (ref "C16") (pin "2") (pinfunction "2_2") (pintype "passive"))
      (node (ref "C2") (pin "2") (pinfunction "2_2") (pintype "passive"))
      (node (ref "C22") (pin "2") (pinfunction "2_2") (pintype "passive"))
      (node (ref "C3") (pin "2") (pinfunction "2_2") (pintype "passive"))
      (node (ref "C4") (pin "2") (pinfunction "2_2") (pintype "passive"))
      (node (ref "C6") (pin "2") (pinfunction "2_2") (pintype "passive"))
      (node (ref "C7") (pin "2") (pinfunction "2_2") (pintype "passive"))
      (node (ref "C8") (pin "2") (pinfunction "2_2") (pintype "passive"))
      (node (ref "C9") (pin "2") (pinfunction "2_2") (pintype "passive"))
      (node (ref "CHARGER") (pin "17") (pinfunction "IUSB1_17") (pintype "bidirectional"))
      (node (ref "CHARGER") (pin "20") (pinfunction "AGND_20") (pintype "bidirectional"))
      (node (ref "CHARGER") (pin "21") (pinfunction "PGND_21") (pintype "bidirectional"))
      (node (ref "CHARGER") (pin "22") (pinfunction "PGND_22") (pintype "bidirectional"))
      (node (ref "CHARGER") (pin "25") (pinfunction "PGND_25") (pintype "bidirectional"))
      (node (ref "CHARGER") (pin "P$10") (pinfunction "PGND_P$10") (pintype "bidirectional"))
      (node (ref "CHARGER") (pin "P$2") (pinfunction "PGND_P$2") (pintype "bidirectional"))
      (node (ref "CHARGER") (pin "P$3") (pinfunction "PGND_P$3") (pintype "bidirectional"))
      (node (ref "CHARGER") (pin "P$4") (pinfunction "PGND_P$4") (pintype "bidirectional"))
      (node (ref "CHARGER") (pin "P$5") (pinfunction "PGND_P$5") (pintype "bidirectional"))
      (node (ref "CHARGER") (pin "P$6") (pinfunction "PGND_P$6") (pintype "bidirectional"))
      (node (ref "CHARGER") (pin "P$7") (pinfunction "PGND_P$7") (pintype "bidirectional"))
      (node (ref "CHARGER") (pin "P$8") (pinfunction "PGND_P$8") (pintype "bidirectional"))
      (node (ref "CHARGER") (pin "P$9") (pinfunction "PGND_P$9") (pintype "bidirectional"))
      (node (ref "C_BAT") (pin "1") (pinfunction "1_1") (pintype "passive"))
      (node (ref "C_DC5_IN") (pin "2") (pinfunction "2_2") (pintype "passive"))
      (node (ref "C_DC5_OUT1") (pin "2") (pinfunction "2_2") (pintype "passive"))
      (node (ref "C_DC5_OUT2") (pin "2") (pinfunction "2_2") (pintype "passive"))
      (node (ref "C_DC5_SS") (pin "2") (pinfunction "2_2") (pintype "passive"))
      (node (ref "C_DRV") (pin "2") (pinfunction "2_2") (pintype "passive"))
      (node (ref "C_IN") (pin "2") (pinfunction "2_2") (pintype "passive"))
      (node (ref "C_OUTS") (pin "2") (pinfunction "2_2") (pintype "passive"))
      (node (ref "C_PMID") (pin "1") (pinfunction "1_1") (pintype "passive"))
      (node (ref "C_SYS") (pin "2") (pinfunction "2_2") (pintype "passive"))
      (node (ref "DC3VLINK") (pin "4") (pinfunction "GND_4") (pintype "passive"))
      (node (ref "DC3VLINK") (pin "GND") (pinfunction "GND_GND") (pintype "passive"))
      (node (ref "DC3VLINK") (pin "GND1") (pinfunction "GND_GND1") (pintype "passive"))
      (node (ref "DC3VLINK") (pin "GND2") (pinfunction "GND_GND2") (pintype "passive"))
      (node (ref "DC3VLINK") (pin "GND3") (pinfunction "GND_GND3") (pintype "passive"))
      (node (ref "DC3VLINK") (pin "GND4") (pinfunction "GND_GND4") (pintype "passive"))
      (node (ref "DC5V") (pin "G1") (pinfunction "GND_G1") (pintype "bidirectional"))
      (node (ref "DC5V") (pin "G2") (pinfunction "GND_G2") (pintype "bidirectional"))
      (node (ref "DC5V") (pin "G3") (pinfunction "GND_G3") (pintype "bidirectional"))
      (node (ref "DC5V") (pin "G4") (pinfunction "GND_G4") (pintype "bidirectional"))
      (node (ref "DC5V") (pin "G5") (pinfunction "GND_G5") (pintype "bidirectional"))
      (node (ref "DC5V") (pin "PAD") (pinfunction "GND_PAD") (pintype "bidirectional"))
      (node (ref "EXT-INTERFACE") (pin "4") (pinfunction "4_4") (pintype "bidirectional"))
      (node (ref "JP-DCIN") (pin "1") (pinfunction "1_1") (pintype "passive"))
      (node (ref "LINK") (pin "GND") (pinfunction "GND_GND") (pintype "bidirectional"))
      (node (ref "LINK") (pin "GND2") (pinfunction "GND1_GND2") (pintype "bidirectional"))
      (node (ref "LINK") (pin "SLEEP") (pinfunction "SLEEP_SLEEP") (pintype "bidirectional"))
      (node (ref "PWR") (pin "2") (pinfunction "2_2") (pintype "passive"))
      (node (ref "PWR") (pin "NC1") (pinfunction "3_NC1") (pintype "passive"))
      (node (ref "PWR") (pin "NC2") (pinfunction "3_NC2") (pintype "passive"))
      (node (ref "PZ1") (pin "GND") (pinfunction "GND_GND") (pintype "bidirectional"))
      (node (ref "P_IN") (pin "4") (pinfunction "GND_4") (pintype "bidirectional"))
      (node (ref "R10") (pin "1") (pinfunction "1_1") (pintype "passive"))
      (node (ref "R16") (pin "1") (pinfunction "1_1") (pintype "passive"))
      (node (ref "R18") (pin "1") (pinfunction "1_1") (pintype "passive"))
      (node (ref "R28") (pin "1") (pinfunction "1_1") (pintype "passive"))
      (node (ref "R51") (pin "1") (pinfunction "1_1") (pintype "passive"))
      (node (ref "R52") (pin "1") (pinfunction "1_1") (pintype "passive"))
      (node (ref "R9") (pin "1") (pinfunction "1_1") (pintype "passive"))
      (node (ref "R_ISET") (pin "1") (pinfunction "1_1") (pintype "passive"))
      (node (ref "R_ISET1") (pin "2") (pinfunction "2_2") (pintype "passive"))
      (node (ref "R_VDPM_B") (pin "1") (pinfunction "1_1") (pintype "passive"))
      (node (ref "SD") (pin "CD2") (pinfunction "CD2_CD2") (pintype "bidirectional"))
      (node (ref "SD") (pin "D6") (pinfunction "D6_D6") (pintype "bidirectional"))
      (node (ref "SD") (pin "GND") (pinfunction "GND_GND") (pintype "bidirectional"))
      (node (ref "SD") (pin "GND1") (pinfunction "GND_GND1") (pintype "bidirectional"))
      (node (ref "SD") (pin "GND2") (pinfunction "GND_GND2") (pintype "bidirectional"))
      (node (ref "SD") (pin "GND3") (pinfunction "GND_GND3") (pintype "bidirectional"))
      (node (ref "SREC") (pin "O") (pinfunction "O_O") (pintype "bidirectional"))
      (node (ref "T2") (pin "1") (pinfunction "S_1") (pintype "passive"))
      (node (ref "T2") (pin "4") (pinfunction "S_4") (pintype "passive"))
      (node (ref "T3") (pin "1") (pinfunction "S_1") (pintype "passive"))
      (node (ref "TRIG-IN") (pin "2") (pinfunction "2_2") (pintype "bidirectional"))
      (node (ref "TRIG-IN") (pin "P1") (pinfunction "GND_P1") (pintype "bidirectional"))
      (node (ref "TRIG-IN") (pin "P2") (pinfunction "GND_P2") (pintype "bidirectional"))
      (node (ref "TRIG-OUT") (pin "7") (pinfunction "7_7") (pintype "bidirectional"))
      (node (ref "TRIG-OUT") (pin "P1") (pinfunction "GND_P1") (pintype "bidirectional"))
      (node (ref "TRIG-OUT") (pin "P2") (pinfunction "GND_P2") (pintype "bidirectional"))
      (node (ref "TVS1") (pin "1") (pinfunction "G_1") (pintype "bidirectional"))
      (node (ref "TVS10") (pin "2") (pinfunction "IO_2") (pintype "bidirectional"))
      (node (ref "TVS2") (pin "2") (pinfunction "IO_2") (pintype "bidirectional"))
      (node (ref "TVS3") (pin "2") (pinfunction "IO_2") (pintype "bidirectional"))
      (node (ref "TVS4") (pin "1") (pinfunction "G_1") (pintype "bidirectional"))
      (node (ref "TVS5") (pin "1") (pinfunction "G_1") (pintype "bidirectional"))
      (node (ref "TVS6") (pin "1") (pinfunction "G_1") (pintype "bidirectional"))
      (node (ref "TVS7") (pin "1") (pinfunction "G_1") (pintype "bidirectional"))
      (node (ref "TVS8") (pin "1") (pinfunction "G_1") (pintype "bidirectional"))
      (node (ref "TVS9") (pin "1") (pinfunction "G_1") (pintype "bidirectional"))
      (node (ref "U$1") (pin "GNDA") (pinfunction "GNDA_GNDA") (pintype "bidirectional"))
      (node (ref "U$1") (pin "GNDA1") (pinfunction "GNDA1_GNDA1") (pintype "bidirectional"))
      (node (ref "U$1") (pin "GNDA2") (pinfunction "GNDA2_GNDA2") (pintype "bidirectional"))
      (node (ref "U$1") (pin "GNDA3") (pinfunction "GNDA3_GNDA3") (pintype "bidirectional"))
      (node (ref "U$1") (pin "GND_1") (pinfunction "GND_1_GND_1") (pintype "bidirectional"))
      (node (ref "U$1") (pin "GND_2") (pinfunction "GND_2_GND_2") (pintype "bidirectional"))
      (node (ref "U$1") (pin "GND_3") (pinfunction "GND_3_GND_3") (pintype "bidirectional"))
      (node (ref "U$1") (pin "GND_4") (pinfunction "GND_4_GND_4") (pintype "bidirectional"))
      (node (ref "U$2") (pin "GND1") (pinfunction "GND1_GND1") (pintype "bidirectional"))
      (node (ref "U$2") (pin "GND2") (pinfunction "GND2_GND2") (pintype "bidirectional"))
      (node (ref "U$2") (pin "GND3") (pinfunction "GND3_GND3") (pintype "bidirectional"))
      (node (ref "U$2") (pin "GND4") (pinfunction "GND4_GND4") (pintype "bidirectional"))
      (node (ref "U1") (pin "10") (pinfunction "DEN(G)_10") (pintype "bidirectional"))
      (node (ref "U1") (pin "2") (pinfunction "GND_2") (pintype "bidirectional"))
      (node (ref "U1") (pin "3") (pinfunction "GND_3") (pintype "bidirectional"))
      (node (ref "U1") (pin "4") (pinfunction "GND_4") (pintype "bidirectional"))
      (node (ref "U1") (pin "5") (pinfunction "GND_5") (pintype "bidirectional"))
      (node (ref "U1") (pin "6") (pinfunction "GND_6") (pintype "bidirectional"))
      (node (ref "U2") (pin "1") (pinfunction "GND_1") (pintype "bidirectional"))
      (node (ref "U2") (pin "11") (pinfunction "GND_11") (pintype "bidirectional"))
      (node (ref "U2") (pin "13") (pinfunction "GND_13") (pintype "bidirectional"))
      (node (ref "U2") (pin "15") (pinfunction "GND_15") (pintype "bidirectional"))
      (node (ref "U2") (pin "5") (pinfunction "GND_5") (pintype "bidirectional"))
      (node (ref "U2") (pin "9") (pinfunction "GND_9") (pintype "bidirectional"))
      (node (ref "U4") (pin "2") (pinfunction "GND_2") (pintype "input"))
      (node (ref "U7") (pin "11") (pinfunction "GND_11") (pintype "bidirectional"))
      (node (ref "U7") (pin "EPAD") (pinfunction "GND_EPAD") (pintype "bidirectional"))
      (node (ref "U9") (pin "11") (pinfunction "GND_11") (pintype "bidirectional"))
      (node (ref "U9") (pin "EPAD") (pinfunction "GND_EPAD") (pintype "bidirectional"))
      (node (ref "UART-EXT") (pin "4") (pinfunction "4_4") (pintype "bidirectional"))
      (node (ref "UART-EXT") (pin "P1") (pinfunction "GND_P1") (pintype "bidirectional"))
      (node (ref "UART-EXT") (pin "P2") (pinfunction "GND_P2") (pintype "bidirectional"))
      (node (ref "USB") (pin "5") (pinfunction "GND_5") (pintype "passive"))
      (node (ref "USB") (pin "PAD1") (pinfunction "GND_PAD1") (pintype "passive"))
      (node (ref "USB") (pin "PAD2") (pinfunction "GND_PAD2") (pintype "passive"))
      (node (ref "USB") (pin "PAD3") (pinfunction "GND_PAD3") (pintype "passive"))
      (node (ref "USB") (pin "PAD4") (pinfunction "GND_PAD4") (pintype "passive"))
      (node (ref "USB") (pin "PAD5") (pinfunction "GND_PAD5") (pintype "passive"))
      (node (ref "USB") (pin "PAD6") (pinfunction "GND_PAD6") (pintype "passive"))
      (node (ref "USBREG") (pin "2") (pinfunction "GND_2") (pintype "bidirectional"))
      (node (ref "X1") (pin "1") (pinfunction "GND_1") (pintype "passive"))
      (node (ref "X1") (pin "2") (pinfunction "GND_2") (pintype "passive"))
    )
    (net (code "26") (name "GP12_PWM0_TRIG_OUT") (class "Default")
      (node (ref "TRIG-OUT") (pin "2") (pinfunction "2_2") (pintype "bidirectional"))
      (node (ref "TVS3") (pin "1") (pinfunction "G_1") (pintype "bidirectional"))
      (node (ref "U2") (pin "35") (pinfunction "GP12_PWM0_35") (pintype "bidirectional"))
    )
    (net (code "27") (name "GP13_PWM1-LINKSTATUS") (class "Default")
      (node (ref "U2") (pin "33") (pinfunction "GP13_PWM1_33") (pintype "bidirectional"))
      (node (ref "U7") (pin "6") (pinfunction "A5_6") (pintype "bidirectional"))
    )
    (net (code "28") (name "GP14-ACT-UART2") (class "Default")
      (node (ref "R4") (pin "2") (pinfunction "2_2") (pintype "passive"))
      (node (ref "U2") (pin "48") (pinfunction "GP14_48") (pintype "bidirectional"))
    )
    (net (code "29") (name "GP15-LEDSAT") (class "Default")
      (node (ref "T3") (pin "2") (pinfunction "G_2") (pintype "passive"))
      (node (ref "U2") (pin "42") (pinfunction "GP15_42") (pintype "bidirectional"))
    )
    (net (code "30") (name "GP19_I2C_1_SCL") (class "Default")
      (node (ref "JP-SCL") (pin "3") (pinfunction "3_3") (pintype "passive"))
      (node (ref "R52") (pin "2") (pinfunction "2_2") (pintype "passive"))
      (node (ref "U1") (pin "21") (pinfunction "SCL_21") (pintype "bidirectional"))
      (node (ref "U2") (pin "41") (pinfunction "GP19_I2C_1_SCL_41") (pintype "bidirectional"))
    )
    (net (code "31") (name "GP20_I2C_1_SDA") (class "Default")
      (node (ref "JP-SDA") (pin "3") (pinfunction "3_3") (pintype "passive"))
      (node (ref "R51") (pin "2") (pinfunction "2_2") (pintype "passive"))
      (node (ref "U1") (pin "24") (pinfunction "SDA_24") (pintype "bidirectional"))
      (node (ref "U2") (pin "43") (pinfunction "GP20_I2C_1_SDA_43") (pintype "bidirectional"))
    )
    (net (code "32") (name "GP27_I2C_6_SCL") (class "Default")
      (node (ref "JP-SCL") (pin "1") (pinfunction "1_1") (pintype "passive"))
      (node (ref "U2") (pin "45") (pinfunction "GP27_I2C_6_SCL_45") (pintype "bidirectional"))
    )
    (net (code "33") (name "GP28_I2C_6_SDA") (class "Default")
      (node (ref "JP-SDA") (pin "1") (pinfunction "1_1") (pintype "passive"))
      (node (ref "U2") (pin "47") (pinfunction "GP28_I2C_6_SDA_47") (pintype "bidirectional"))
    )
    (net (code "34") (name "GP40_I2S_2_CLK") (class "Default")
      (node (ref "U2") (pin "52") (pinfunction "GP40_I2S_2_CLK_52") (pintype "bidirectional"))
    )
    (net (code "35") (name "GP41_I2S_2_FS") (class "Default")
      (node (ref "U2") (pin "54") (pinfunction "GP41_I2S_2_FS_54") (pintype "bidirectional"))
    )
    (net (code "36") (name "GP42_I2S_2_RXD") (class "Default")
      (node (ref "U2") (pin "50") (pinfunction "GP42_I2S_2_RXD_50") (pintype "bidirectional"))
    )
    (net (code "37") (name "GP43_I2S_2_TXD") (class "Default")
      (node (ref "U2") (pin "56") (pinfunction "GP43_I2S_2_TXD_56") (pintype "bidirectional"))
    )
    (net (code "38") (name "GP44-STARTREC") (class "Default")
      (node (ref "EXT-INTERFACE") (pin "1") (pinfunction "1_1") (pintype "bidirectional"))
      (node (ref "R15") (pin "2") (pinfunction "2_2") (pintype "passive"))
      (node (ref "SREC") (pin "I") (pinfunction "I_I") (pintype "bidirectional"))
      (node (ref "TVS9") (pin "2") (pinfunction "IO_2") (pintype "bidirectional"))
      (node (ref "U2") (pin "24") (pinfunction "GP44_24") (pintype "bidirectional"))
    )
    (net (code "39") (name "GP45-FLASH") (class "Default")
      (node (ref "U2") (pin "26") (pinfunction "GP45_26") (pintype "bidirectional"))
      (node (ref "U7") (pin "8") (pinfunction "A7_8") (pintype "bidirectional"))
    )
    (net (code "40") (name "GP46-CMD-TRIG-EXT") (class "Default")
      (node (ref "U2") (pin "28") (pinfunction "GP46_28") (pintype "bidirectional"))
      (node (ref "U7") (pin "7") (pinfunction "A6_7") (pintype "bidirectional"))
    )
    (net (code "41") (name "GP47-EN-DC5V") (class "Default")
      (node (ref "R7") (pin "2") (pinfunction "2_2") (pintype "passive"))
      (node (ref "U2") (pin "30") (pinfunction "GP47_30") (pintype "bidirectional"))
    )
    (net (code "42") (name "GP48-LEDTRIGIN") (class "Default")
      (node (ref "T2") (pin "5") (pinfunction "G_5") (pintype "passive"))
      (node (ref "U2") (pin "32") (pinfunction "GP48_32") (pintype "bidirectional"))
    )
    (net (code "43") (name "GP49-LINKCONFIG") (class "Default")
      (node (ref "U2") (pin "34") (pinfunction "GP49_34") (pintype "bidirectional"))
      (node (ref "U7") (pin "9") (pinfunction "A8_9") (pintype "bidirectional"))
    )
    (net (code "44") (name "GP77_SD_0_CD#") (class "Default")
      (node (ref "SD") (pin "CD1") (pinfunction "CD1_CD1") (pintype "bidirectional"))
      (node (ref "U2") (pin "60") (pinfunction "GP77_SD_0_CD#_60") (pintype "bidirectional"))
    )
    (net (code "45") (name "GP78_SD_0_CLK") (class "Default")
      (node (ref "U2") (pin "58") (pinfunction "GP78_SD_0_CLK_58") (pintype "bidirectional"))
      (node (ref "U9") (pin "5") (pinfunction "A4_5") (pintype "bidirectional"))
    )
    (net (code "46") (name "GP79_SD_0_CMD") (class "Default")
      (node (ref "U2") (pin "62") (pinfunction "GP79_SD_0_CMD_62") (pintype "bidirectional"))
      (node (ref "U9") (pin "4") (pinfunction "A3_4") (pintype "bidirectional"))
    )
    (net (code "47") (name "GP80_SD_0_DAT0") (class "Default")
      (node (ref "U2") (pin "66") (pinfunction "GP80_SD_0_DAT0_66") (pintype "bidirectional"))
      (node (ref "U9") (pin "6") (pinfunction "A5_6") (pintype "bidirectional"))
    )
    (net (code "48") (name "GP81_SD_0_DAT1") (class "Default")
      (node (ref "U2") (pin "70") (pinfunction "GP81_SD_0_DAT1_70") (pintype "bidirectional"))
      (node (ref "U9") (pin "7") (pinfunction "A6_7") (pintype "bidirectional"))
    )
    (net (code "49") (name "GP82_SD_0_DAT2") (class "Default")
      (node (ref "U2") (pin "64") (pinfunction "GP82_SD_0_DAT2_64") (pintype "bidirectional"))
      (node (ref "U9") (pin "1") (pinfunction "A1_1") (pintype "bidirectional"))
    )
    (net (code "50") (name "GP83_SD_0_DAT3") (class "Default")
      (node (ref "U2") (pin "68") (pinfunction "GP83_SD_0_DAT3_68") (pintype "bidirectional"))
      (node (ref "U9") (pin "3") (pinfunction "A2_3") (pintype "bidirectional"))
    )
    (net (code "51") (name "GP84_SD_CLK_FB") (class "Default")
      (node (ref "U2") (pin "44") (pinfunction "GP84_SD_CLK_FB_44") (pintype "bidirectional"))
      (node (ref "U9") (pin "8") (pinfunction "A7_8") (pintype "bidirectional"))
    )
    (net (code "52") (name "GP109_SPI_2_CLK") (class "Default")
      (node (ref "U2") (pin "55") (pinfunction "GP109_SPI_2_CLK_55") (pintype "bidirectional"))
    )
    (net (code "53") (name "GP110_SPI_2_FS0") (class "Default")
      (node (ref "U2") (pin "53") (pinfunction "GP110_SPI_2_FS0_53") (pintype "bidirectional"))
    )
    (net (code "54") (name "GP111_SPI_2_FS1") (class "Default")
      (node (ref "U2") (pin "51") (pinfunction "GP111_SPI_2_FS1_51") (pintype "bidirectional"))
    )
    (net (code "55") (name "GP114_SPI_2_RXD") (class "Default")
      (node (ref "U2") (pin "59") (pinfunction "GP114_SPI_2_RXD_59") (pintype "bidirectional"))
    )
    (net (code "56") (name "GP115_SPI_2_TXD") (class "Default")
      (node (ref "U2") (pin "57") (pinfunction "GP115_SPI_2_TXD_57") (pintype "bidirectional"))
    )
    (net (code "57") (name "GP128_UART_1_CTS") (class "Default")
      (node (ref "U2") (pin "65") (pinfunction "GP128_UART_1_CTS_65") (pintype "bidirectional"))
    )
    (net (code "58") (name "GP129_UART_1_RTS") (class "Default")
      (node (ref "U2") (pin "63") (pinfunction "GP129_UART_1_RTS_63") (pintype "bidirectional"))
    )
    (net (code "59") (name "GP130_UART_1_RX") (class "Default")
      (node (ref "U2") (pin "61") (pinfunction "GP130_UART_1_RX_61") (pintype "bidirectional"))
      (node (ref "U7") (pin "4") (pinfunction "A3_4") (pintype "bidirectional"))
    )
    (net (code "60") (name "GP131_UART_1_TX") (class "Default")
      (node (ref "U2") (pin "46") (pinfunction "GP131_UART_1_TX_46") (pintype "bidirectional"))
      (node (ref "U7") (pin "5") (pinfunction "A4_5") (pintype "bidirectional"))
    )
    (net (code "61") (name "GP134_UART_2_RX") (class "Default")
      (node (ref "U2") (pin "22") (pinfunction "GP134_UART_2_RX_22") (pintype "bidirectional"))
      (node (ref "U7") (pin "1") (pinfunction "A1_1") (pintype "bidirectional"))
    )
    (net (code "62") (name "GP135_UART_2_TX") (class "Default")
      (node (ref "U2") (pin "27") (pinfunction "GP135_UART_2_TX_27") (pintype "bidirectional"))
      (node (ref "U7") (pin "3") (pinfunction "A2_3") (pintype "bidirectional"))
    )
    (net (code "63") (name "GP165-LEDREC") (class "Default")
      (node (ref "T2") (pin "2") (pinfunction "G_2") (pintype "passive"))
      (node (ref "U2") (pin "25") (pinfunction "GP165_25") (pintype "bidirectional"))
    )
    (net (code "64") (name "GP182_PWM2-PPS") (class "Default")
      (node (ref "U2") (pin "37") (pinfunction "GP182_PWM2_37") (pintype "bidirectional"))
      (node (ref "U9") (pin "9") (pinfunction "A8_9") (pintype "bidirectional"))
    )
    (net (code "65") (name "GP183_PWM3") (class "Default")
      (node (ref "U2") (pin "39") (pinfunction "GP183_PWM3_39") (pintype "bidirectional"))
    )
    (net (code "66") (name "INT1_XM") (class "Default")
      (node (ref "U1") (pin "13") (pinfunction "INT1(XM)_13") (pintype "bidirectional"))
    )
    (net (code "67") (name "INT2_XM") (class "Default")
      (node (ref "U1") (pin "14") (pinfunction "INT2(XM)_14") (pintype "bidirectional"))
    )
    (net (code "68") (name "INT_G") (class "Default")
      (node (ref "U1") (pin "11") (pinfunction "INT(G)_11") (pintype "bidirectional"))
    )
    (net (code "69") (name "MSIC_SLP_CLK") (class "Default")
      (node (ref "U2") (pin "7") (pinfunction "MSIC_SLP_CLK_7") (pintype "bidirectional"))
    )
    (net (code "70") (name "Net-(5VACCLIM-ILIM)") (class "Default")
      (node (ref "5VACCLIM") (pin "5") (pinfunction "ILIM_5") (pintype "bidirectional"))
      (node (ref "R9") (pin "2") (pinfunction "2_2") (pintype "passive"))
    )
    (net (code "71") (name "Net-(C9-Pad1)") (class "Default")
      (node (ref "C9") (pin "1") (pinfunction "1_1") (pintype "passive"))
      (node (ref "JP-ENABLE-UART2") (pin "1") (pinfunction "1_1") (pintype "passive"))
      (node (ref "R4") (pin "1") (pinfunction "1_1") (pintype "passive"))
    )
    (net (code "72") (name "Net-(CHARGER-BOOT)") (class "Default")
      (node (ref "CHARGER") (pin "2") (pinfunction "BOOT_2") (pintype "bidirectional"))
      (node (ref "C_BOOT") (pin "2") (pinfunction "2_2") (pintype "passive"))
    )
    (net (code "73") (name "Net-(CHARGER-CE)") (class "Default")
      (node (ref "CHARGER") (pin "4") (pinfunction "CE_4") (pintype "bidirectional"))
      (node (ref "R_ISET1") (pin "1") (pinfunction "1_1") (pintype "passive"))
    )
    (net (code "74") (name "Net-(CHARGER-CHG)") (class "Default")
      (node (ref "CHARGER") (pin "13") (pinfunction "CHG_13") (pintype "bidirectional"))
      (node (ref "R_CHG") (pin "1") (pinfunction "1_1") (pintype "passive"))
    )
    (net (code "75") (name "Net-(CHARGER-ISET)") (class "Default")
      (node (ref "CHARGER") (pin "12") (pinfunction "ISET_12") (pintype "bidirectional"))
      (node (ref "R_ISET") (pin "2") (pinfunction "2_2") (pintype "passive"))
    )
    (net (code "76") (name "Net-(CHARGER-IUSB2)") (class "Default")
      (node (ref "CHARGER") (pin "14") (pinfunction "IUSB3_14") (pintype "bidirectional"))
      (node (ref "CHARGER") (pin "16") (pinfunction "IUSB2_16") (pintype "bidirectional"))
      (node (ref "D_IUSB") (pin "3") (pinfunction "CC_3") (pintype "passive"))
    )
    (net (code "77") (name "Net-(CHARGER-PG)") (class "Default")
      (node (ref "CHARGER") (pin "10") (pinfunction "PG_10") (pintype "bidirectional"))
      (node (ref "R_PG") (pin "1") (pinfunction "1_1") (pintype "passive"))
    )
    (net (code "78") (name "Net-(CHARGER-PMID)") (class "Default")
      (node (ref "CHARGER") (pin "1") (pinfunction "PMID_1") (pintype "bidirectional"))
      (node (ref "C_PMID") (pin "2") (pinfunction "2_2") (pintype "passive"))
    )
    (net (code "79") (name "Net-(CHARGER-SW-Pad23)") (class "Default")
      (node (ref "CHARGER") (pin "23") (pinfunction "SW_23") (pintype "bidirectional"))
      (node (ref "CHARGER") (pin "24") (pinfunction "SW_24") (pintype "bidirectional"))
      (node (ref "C_BOOT") (pin "1") (pinfunction "1_1") (pintype "passive"))
      (node (ref "L_SW") (pin "1") (pinfunction "1_1") (pintype "passive"))
    )
    (net (code "80") (name "Net-(CHARGER-VDPM)") (class "Default")
      (node (ref "CHARGER") (pin "15") (pinfunction "VDPM_15") (pintype "bidirectional"))
      (node (ref "R_VDPM_B") (pin "2") (pinfunction "2_2") (pintype "passive"))
      (node (ref "R_VDPM_T") (pin "1") (pinfunction "1_1") (pintype "passive"))
    )
    (net (code "81") (name "Net-(CHARGING-PadC)") (class "Default")
      (node (ref "CHARGING") (pin "C") (pinfunction "C_C") (pintype "passive"))
      (node (ref "R_CHG") (pin "2") (pinfunction "2_2") (pintype "passive"))
    )
    (net (code "82") (name "Net-(D-ON-PadC)") (class "Default")
      (node (ref "D-ON") (pin "C") (pinfunction "C_C") (pintype "passive"))
      (node (ref "R28") (pin "2") (pinfunction "2_2") (pintype "passive"))
    )
    (net (code "83") (name "Net-(D-REC-PadC)") (class "Default")
      (node (ref "D-REC") (pin "C") (pinfunction "C_C") (pintype "passive"))
      (node (ref "R19") (pin "1") (pinfunction "1_1") (pintype "passive"))
    )
    (net (code "84") (name "Net-(D-SAT-PadC)") (class "Default")
      (node (ref "D-SAT") (pin "C") (pinfunction "C_C") (pintype "passive"))
      (node (ref "R24") (pin "1") (pinfunction "1_1") (pintype "passive"))
    )
    (net (code "85") (name "Net-(D-TRIGGER-PadC)") (class "Default")
      (node (ref "D-TRIGGER") (pin "C") (pinfunction "C_C") (pintype "passive"))
      (node (ref "R20") (pin "1") (pinfunction "1_1") (pintype "passive"))
    )
    (net (code "86") (name "Net-(DC3VLINK-NR{slash}FB)") (class "Default")
      (node (ref "C16") (pin "1") (pinfunction "1_1") (pintype "passive"))
      (node (ref "DC3VLINK") (pin "3") (pinfunction "NR/FB_3") (pintype "input"))
    )
    (net (code "87") (name "Net-(DC5V-FB)") (class "Default")
      (node (ref "BLM5V1") (pin "1") (pinfunction "1_1") (pintype "bidirectional"))
      (node (ref "BLM5V2") (pin "1") (pinfunction "1_1") (pintype "bidirectional"))
      (node (ref "C_DC5_OUT1") (pin "1") (pinfunction "1_1") (pintype "passive"))
      (node (ref "C_DC5_OUT2") (pin "1") (pinfunction "1_1") (pintype "passive"))
      (node (ref "C_OUTS") (pin "1") (pinfunction "1_1") (pintype "passive"))
      (node (ref "DC5V") (pin "P$3") (pinfunction "VOUT_P$3") (pintype "bidirectional"))
      (node (ref "DC5V") (pin "P$4") (pinfunction "VOUT1_P$4") (pintype "bidirectional"))
      (node (ref "DC5V") (pin "P$7") (pinfunction "FB_P$7") (pintype "bidirectional"))
    )
    (net (code "88") (name "Net-(DC5V-SS)") (class "Default")
      (node (ref "C_DC5_SS") (pin "1") (pinfunction "1_1") (pintype "passive"))
      (node (ref "DC5V") (pin "P$6") (pinfunction "SS_P$6") (pintype "bidirectional"))
    )
    (net (code "89") (name "Net-(DC5V-SW)") (class "Default")
      (node (ref "DC5V") (pin "P$1") (pinfunction "SW_P$1") (pintype "bidirectional"))
      (node (ref "DC5V") (pin "P$2") (pinfunction "SW1_P$2") (pintype "bidirectional"))
      (node (ref "L_DC5_SW") (pin "P$2") (pinfunction "2_P$2") (pintype "passive"))
    )
    (net (code "90") (name "Net-(JP_LINK-Pad2)") (class "Default")
      (node (ref "JP_LINK") (pin "2") (pinfunction "2_2") (pintype "passive"))
      (node (ref "LINK") (pin "RESET") (pinfunction "RESET_RESET") (pintype "bidirectional"))
      (node (ref "LINK") (pin "VCC") (pinfunction "VCC_VCC") (pintype "bidirectional"))
    )
    (net (code "91") (name "Net-(POWER-PadC)") (class "Default")
      (node (ref "POWER") (pin "C") (pinfunction "C_C") (pintype "passive"))
      (node (ref "R_PG") (pin "2") (pinfunction "2_2") (pintype "passive"))
    )
    (net (code "92") (name "Net-(PTC1-I)") (class "Default")
      (node (ref "PTC1") (pin "P$1") (pinfunction "I_P$1") (pintype "bidirectional"))
      (node (ref "PZ1") (pin "OUT") (pinfunction "OUT_OUT") (pintype "bidirectional"))
      (node (ref "U$1") (pin "VIN") (pinfunction "VIN_VIN") (pintype "bidirectional"))
    )
    (net (code "93") (name "Net-(PTC1-O)") (class "Default")
      (node (ref "PTC1") (pin "P$2") (pinfunction "O_P$2") (pintype "bidirectional"))
      (node (ref "U$1") (pin "LNA_PWR") (pinfunction "LNA_PWR_LNA_PWR") (pintype "bidirectional"))
    )
    (net (code "94") (name "Net-(U$1-PadANT)") (class "Default")
      (node (ref "U$1") (pin "ANT") (pinfunction "ANT_ANT") (pintype "bidirectional"))
      (node (ref "U$2") (pin "ANT") (pinfunction "ANT_ANT") (pintype "bidirectional"))
    )
    (net (code "95") (name "Net-(U1-C1)") (class "Default")
      (node (ref "C6") (pin "1") (pinfunction "1_1") (pintype "passive"))
      (node (ref "U1") (pin "7") (pinfunction "C1_7") (pintype "bidirectional"))
    )
    (net (code "96") (name "Net-(U1-SETC)") (class "Default")
      (node (ref "C5") (pin "2") (pinfunction "2_2") (pintype "passive"))
      (node (ref "U1") (pin "8") (pinfunction "SETC_8") (pintype "bidirectional"))
    )
    (net (code "97") (name "Net-(U1-SETP)") (class "Default")
      (node (ref "C5") (pin "1") (pinfunction "1_1") (pintype "passive"))
      (node (ref "U1") (pin "9") (pinfunction "SETP_9") (pintype "bidirectional"))
    )
    (net (code "98") (name "Net-(U2-DCIN)") (class "Default")
      (node (ref "JP-DCIN") (pin "2") (pinfunction "2_2") (pintype "passive"))
      (node (ref "U2") (pin "14") (pinfunction "DCIN_14") (pintype "bidirectional"))
    )
    (net (code "99") (name "Net-(U7-OE)") (class "Default")
      (node (ref "JP-ENABLE-UART2") (pin "2") (pinfunction "2_2") (pintype "passive"))
      (node (ref "U7") (pin "10") (pinfunction "OE_10") (pintype "bidirectional"))
    )
    (net (code "100") (name "Net-(U9-B1)") (class "Default")
      (node (ref "SD") (pin "D1") (pinfunction "D1_D1") (pintype "bidirectional"))
      (node (ref "U9") (pin "20") (pinfunction "B1_20") (pintype "bidirectional"))
    )
    (net (code "101") (name "Net-(U9-B2)") (class "Default")
      (node (ref "SD") (pin "D2") (pinfunction "D2_D2") (pintype "bidirectional"))
      (node (ref "U9") (pin "18") (pinfunction "B2_18") (pintype "bidirectional"))
    )
    (net (code "102") (name "Net-(U9-B3)") (class "Default")
      (node (ref "SD") (pin "D3") (pinfunction "D3_D3") (pintype "bidirectional"))
      (node (ref "U9") (pin "17") (pinfunction "B3_17") (pintype "bidirectional"))
    )
    (net (code "103") (name "Net-(U9-B4)") (class "Default")
      (node (ref "SD") (pin "D5") (pinfunction "D5_D5") (pintype "bidirectional"))
      (node (ref "U9") (pin "13") (pinfunction "B7_13") (pintype "bidirectional"))
      (node (ref "U9") (pin "16") (pinfunction "B4_16") (pintype "bidirectional"))
    )
    (net (code "104") (name "Net-(U9-B5)") (class "Default")
      (node (ref "SD") (pin "D7") (pinfunction "D7_D7") (pintype "bidirectional"))
      (node (ref "U9") (pin "15") (pinfunction "B5_15") (pintype "bidirectional"))
    )
    (net (code "105") (name "Net-(U9-B6)") (class "Default")
      (node (ref "SD") (pin "D8") (pinfunction "D8_D8") (pintype "bidirectional"))
      (node (ref "U9") (pin "14") (pinfunction "B6_14") (pintype "bidirectional"))
    )
    (net (code "106") (name "Net-(USBREG-ILIM)") (class "Default")
      (node (ref "R16") (pin "2") (pinfunction "2_2") (pintype "passive"))
      (node (ref "USBREG") (pin "5") (pinfunction "ILIM_5") (pintype "bidirectional"))
    )
    (net (code "107") (name "Net-(X1-SIGNAL)") (class "Default")
      (node (ref "LINK") (pin "ANT") (pinfunction "ANT_ANT") (pintype "bidirectional"))
      (node (ref "X1") (pin "3") (pinfunction "SIGNAL_3") (pintype "passive"))
    )
    (net (code "108") (name "OSC_CLK_OUT") (class "Default")
      (node (ref "U2") (pin "67") (pinfunction "OSC_CLK_OUT_0_67") (pintype "bidirectional"))
    )
    (net (code "109") (name "PSW") (class "Default")
      (node (ref "R18") (pin "2") (pinfunction "2_2") (pintype "passive"))
      (node (ref "U2") (pin "21") (pinfunction "PSW_21") (pintype "bidirectional"))
      (node (ref "USBREG") (pin "3") (pinfunction "EN_3") (pintype "bidirectional"))
    )
    (net (code "110") (name "PWRBTN#") (class "Default")
      (node (ref "R3") (pin "2") (pinfunction "2_2") (pintype "passive"))
      (node (ref "U2") (pin "17") (pinfunction "PWRBTN#_17") (pintype "bidirectional"))
    )
    (net (code "111") (name "RCVR_MODE") (class "Default")
      (node (ref "U2") (pin "31") (pinfunction "RCVR_MODE_31") (pintype "bidirectional"))
    )
    (net (code "112") (name "RESET_OUT#") (class "Default")
      (node (ref "U2") (pin "36") (pinfunction "RESET_OUT#_36") (pintype "bidirectional"))
    )
    (net (code "113") (name "SCL_CAM") (class "Default")
      (node (ref "JP-SCL") (pin "2") (pinfunction "2_2") (pintype "passive"))
      (node (ref "TRIG-OUT") (pin "4") (pinfunction "4_4") (pintype "bidirectional"))
      (node (ref "TVS4") (pin "2") (pinfunction "IO_2") (pintype "bidirectional"))
    )
    (net (code "114") (name "SDA_CAM") (class "Default")
      (node (ref "JP-SDA") (pin "2") (pinfunction "2_2") (pintype "passive"))
      (node (ref "TRIG-OUT") (pin "5") (pinfunction "5_5") (pintype "bidirectional"))
      (node (ref "TVS5") (pin "2") (pinfunction "IO_2") (pintype "bidirectional"))
    )
    (net (code "115") (name "SDO_G") (class "Default")
      (node (ref "R6") (pin "1") (pinfunction "1_1") (pintype "passive"))
      (node (ref "U1") (pin "22") (pinfunction "SDO(G)_22") (pintype "bidirectional"))
    )
    (net (code "116") (name "SDO_XM") (class "Default")
      (node (ref "R5") (pin "1") (pinfunction "1_1") (pintype "passive"))
      (node (ref "U1") (pin "23") (pinfunction "SDO(XM)_23") (pintype "bidirectional"))
    )
    (net (code "117") (name "USB_DN") (class "Default")
      (node (ref "U2") (pin "18") (pinfunction "USB_DN_18") (pintype "bidirectional"))
      (node (ref "USB") (pin "2") (pinfunction "D-_2") (pintype "bidirectional"))
    )
    (net (code "118") (name "USB_DP") (class "Default")
      (node (ref "U2") (pin "16") (pinfunction "USB_DP_16") (pintype "bidirectional"))
      (node (ref "USB") (pin "3") (pinfunction "D+_3") (pintype "bidirectional"))
    )
    (net (code "119") (name "USB_ID") (class "Default")
      (node (ref "U2") (pin "3") (pinfunction "USB_ID_3") (pintype "bidirectional"))
      (node (ref "USB") (pin "4") (pinfunction "ID_4") (pintype "bidirectional"))
    )
    (net (code "120") (name "USB_VBUS") (class "Default")
      (node (ref "C22") (pin "1") (pinfunction "1_1") (pintype "passive"))
      (node (ref "D_IN") (pin "A") (pinfunction "A_A") (pintype "passive"))
      (node (ref "U2") (pin "20") (pinfunction "USB_VBUS_20") (pintype "bidirectional"))
      (node (ref "USB") (pin "1") (pinfunction "VCC_1") (pintype "power_in"))
      (node (ref "USBREG") (pin "6") (pinfunction "VOUT_6") (pintype "bidirectional"))
    )
    (net (code "121") (name "V3.3VLINK") (class "Default")
      (node (ref "C15") (pin "1") (pinfunction "1_1") (pintype "passive"))
      (node (ref "DC3VLINK") (pin "1") (pinfunction "OUT_1") (pintype "output"))
      (node (ref "JP_LINK") (pin "1") (pinfunction "1_1") (pintype "passive"))
    )
    (net (code "122") (name "VCC_RAW_12V") (class "Default")
      (node (ref "D_IN") (pin "C") (pinfunction "C_C") (pintype "passive"))
      (node (ref "PWR") (pin "1") (pinfunction "1_1") (pintype "passive"))
      (node (ref "P_IN") (pin "5") (pinfunction "IN_5") (pintype "bidirectional"))
      (node (ref "P_IN") (pin "6") (pinfunction "IN_6") (pintype "bidirectional"))
      (node (ref "P_IN") (pin "7") (pinfunction "IN_7") (pintype "bidirectional"))
      (node (ref "P_IN") (pin "8") (pinfunction "IN_8") (pintype "bidirectional"))
      (node (ref "P_IN") (pin "PAD") (pinfunction "IN_PAD") (pintype "bidirectional"))
    )
    (net (code "123") (name "V_BAT_BKUP") (class "Default")
      (node (ref "U2") (pin "23") (pinfunction "V_VAT_BKUP_23") (pintype "bidirectional"))
    )
    (net (code "124") (name "V_CH_BAT") (class "Default")
      (node (ref "BATT") (pin "1") (pinfunction "1_1") (pintype "bidirectional"))
      (node (ref "CHARGER") (pin "8") (pinfunction "BAT_8") (pintype "bidirectional"))
      (node (ref "CHARGER") (pin "9") (pinfunction "BAT_9") (pintype "bidirectional"))
      (node (ref "C_BAT") (pin "2") (pinfunction "2_2") (pintype "passive"))
      (node (ref "D_IUSB") (pin "2") (pinfunction "A2_2") (pintype "passive"))
    )
    (net (code "125") (name "V_CH_DRV") (class "Default")
      (node (ref "CHARGER") (pin "3") (pinfunction "DRV_3") (pintype "bidirectional"))
      (node (ref "CHARGER") (pin "5") (pinfunction "TS_5") (pintype "bidirectional"))
      (node (ref "CHARGING") (pin "A") (pinfunction "A_A") (pintype "passive"))
      (node (ref "C_DRV") (pin "1") (pinfunction "1_1") (pintype "passive"))
      (node (ref "D_IUSB") (pin "1") (pinfunction "A1_1") (pintype "passive"))
      (node (ref "POWER") (pin "A") (pinfunction "A_A") (pintype "passive"))
    )
    (net (code "126") (name "V_CH_IN") (class "Default")
      (node (ref "CHARGER") (pin "18") (pinfunction "IN_18") (pintype "bidirectional"))
      (node (ref "CHARGER") (pin "19") (pinfunction "IN_19") (pintype "bidirectional"))
      (node (ref "C_IN") (pin "1") (pinfunction "1_1") (pintype "passive"))
      (node (ref "P_IN") (pin "1") (pinfunction "OUT_1") (pintype "bidirectional"))
      (node (ref "P_IN") (pin "2") (pinfunction "OUT_2") (pintype "bidirectional"))
      (node (ref "P_IN") (pin "3") (pinfunction "OUT_3") (pintype "bidirectional"))
      (node (ref "R_VDPM_T") (pin "2") (pinfunction "2_2") (pintype "passive"))
    )
    (net (code "127") (name "V_CH_SYS") (class "Default")
      (node (ref "CHARGER") (pin "6") (pinfunction "SYS_6") (pintype "bidirectional"))
      (node (ref "CHARGER") (pin "7") (pinfunction "SYS_7") (pintype "bidirectional"))
      (node (ref "C_DC5_IN") (pin "1") (pinfunction "1_1") (pintype "passive"))
      (node (ref "C_SYS") (pin "1") (pinfunction "1_1") (pintype "passive"))
      (node (ref "DC5V") (pin "P$10") (pinfunction "VIN_P$10") (pintype "bidirectional"))
      (node (ref "JP-DCIN") (pin "3") (pinfunction "3_3") (pintype "passive"))
      (node (ref "L_DC5_SW") (pin "P$1") (pinfunction "1_P$1") (pintype "passive"))
      (node (ref "L_SW") (pin "2") (pinfunction "2_2") (pintype "passive"))
      (node (ref "R3") (pin "1") (pinfunction "1_1") (pintype "passive"))
      (node (ref "U2") (pin "2") (pinfunction "VSYS_2") (pintype "bidirectional"))
      (node (ref "U2") (pin "4") (pinfunction "VSYS_4") (pintype "bidirectional"))
      (node (ref "U2") (pin "6") (pinfunction "VSYS_6") (pintype "bidirectional"))
    )
    (net (code "128") (name "X-LEDREC") (class "Default")
      (node (ref "EXT-INTERFACE") (pin "2") (pinfunction "2_2") (pintype "bidirectional"))
      (node (ref "R19") (pin "2") (pinfunction "2_2") (pintype "passive"))
      (node (ref "T2") (pin "6") (pinfunction "D_6") (pintype "passive"))
      (node (ref "TVS8") (pin "2") (pinfunction "IO_2") (pintype "bidirectional"))
    )
    (net (code "129") (name "X-SAT") (class "Default")
      (node (ref "EXT-INTERFACE") (pin "6") (pinfunction "6_6") (pintype "bidirectional"))
      (node (ref "R24") (pin "2") (pinfunction "2_2") (pintype "passive"))
      (node (ref "T3") (pin "6") (pinfunction "D_6") (pintype "passive"))
      (node (ref "TVS6") (pin "2") (pinfunction "IO_2") (pintype "bidirectional"))
    )
    (net (code "130") (name "X-TRIGGER") (class "Default")
      (node (ref "EXT-INTERFACE") (pin "3") (pinfunction "3_3") (pintype "bidirectional"))
      (node (ref "R20") (pin "2") (pinfunction "2_2") (pintype "passive"))
      (node (ref "T2") (pin "3") (pinfunction "D_3") (pintype "passive"))
      (node (ref "TVS7") (pin "2") (pinfunction "IO_2") (pintype "bidirectional"))
    )
    (net (code "131") (name "unconnected-(5VACCLIM-~{FAULT}-Pad4)") (class "Default")
      (node (ref "5VACCLIM") (pin "4") (pinfunction "~{FAULT}_4") (pintype "bidirectional"))
    )
    (net (code "132") (name "unconnected-(CHARGER-BGATE-Pad11)") (class "Default")
      (node (ref "CHARGER") (pin "11") (pinfunction "BGATE_11") (pintype "bidirectional"))
    )
    (net (code "133") (name "unconnected-(DC5V-HYS-PadP$8)") (class "Default")
      (node (ref "DC5V") (pin "P$8") (pinfunction "HYS_P$8") (pintype "bidirectional"))
    )
    (net (code "134") (name "unconnected-(DC5V-PG-PadP$5)") (class "Default")
      (node (ref "DC5V") (pin "P$5") (pinfunction "PG_P$5") (pintype "bidirectional"))
    )
    (net (code "135") (name "unconnected-(T3B-D-Pad3)") (class "Default")
      (node (ref "T3") (pin "3") (pinfunction "D_3") (pintype "passive"))
    )
    (net (code "136") (name "unconnected-(T3B-G-Pad5)") (class "Default")
      (node (ref "T3") (pin "5") (pinfunction "G_5") (pintype "passive"))
    )
    (net (code "137") (name "unconnected-(T3B-S-Pad4)") (class "Default")
      (node (ref "T3") (pin "4") (pinfunction "S_4") (pintype "passive"))
    )
    (net (code "138") (name "unconnected-(U$1-PadNC_1)") (class "Default")
      (node (ref "U$1") (pin "NC_1") (pinfunction "NC_1_NC_1") (pintype "bidirectional"))
    )
    (net (code "139") (name "unconnected-(U$1-PadNC_2)") (class "Default")
      (node (ref "U$1") (pin "NC_2") (pinfunction "NC_2_NC_2") (pintype "bidirectional"))
    )
    (net (code "140") (name "unconnected-(U$1-PadRESETIN)") (class "Default")
      (node (ref "U$1") (pin "RESETIN") (pinfunction "RESETIN_RESETIN") (pintype "bidirectional"))
    )
    (net (code "141") (name "unconnected-(U$1-PadRFU)") (class "Default")
      (node (ref "U$1") (pin "RFU") (pinfunction "RFU_RFU") (pintype "bidirectional"))
    )
    (net (code "142") (name "unconnected-(U$1-PadRTK_LED)") (class "Default")
      (node (ref "U$1") (pin "RTK_LED") (pinfunction "RTK_LED_RTK_LED") (pintype "bidirectional"))
    )
    (net (code "143") (name "unconnected-(U$1-PadSAT_LED)") (class "Default")
      (node (ref "U$1") (pin "SAT_LED") (pinfunction "SAT_LED_SAT_LED") (pintype "bidirectional"))
    )
    (net (code "144") (name "unconnected-(U4-BP-Pad4)") (class "Default")
      (node (ref "U4") (pin "4") (pinfunction "BP_4") (pintype "input"))
    )
  )
)
